# V3_1.net
KiCad netlist of a schematic drawn in EasyEDA Pro
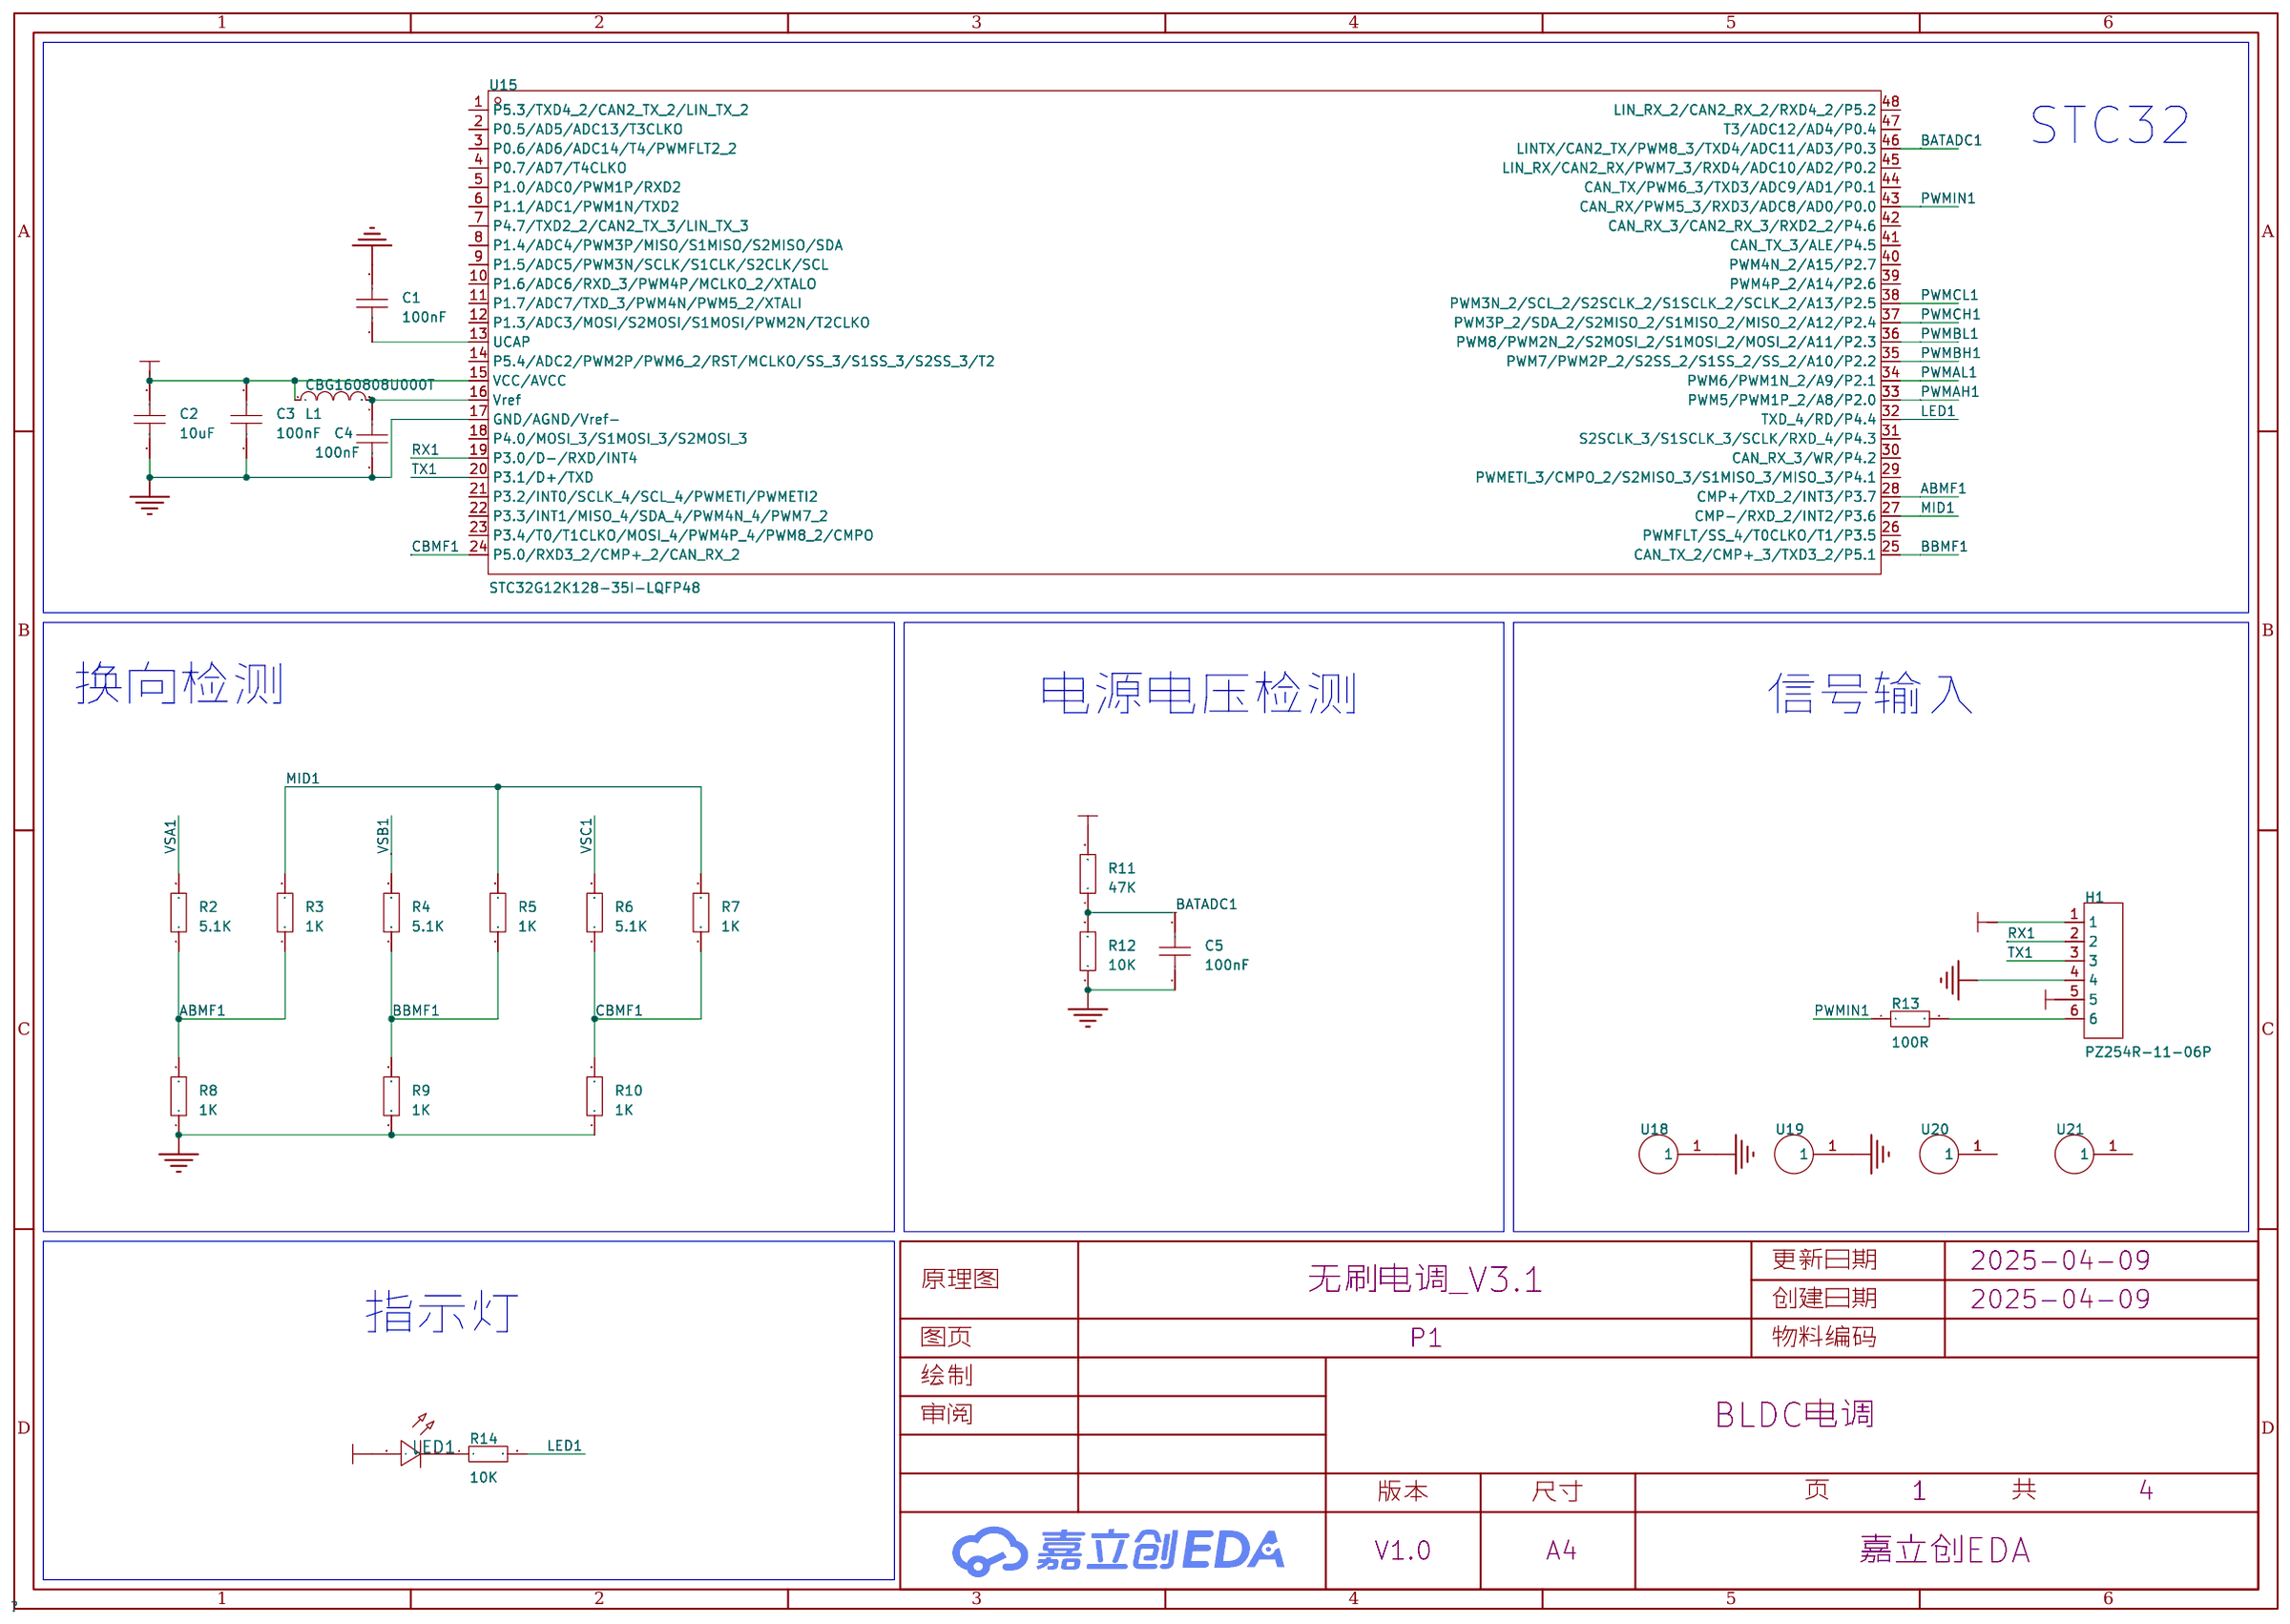
[diagram p0: P1]
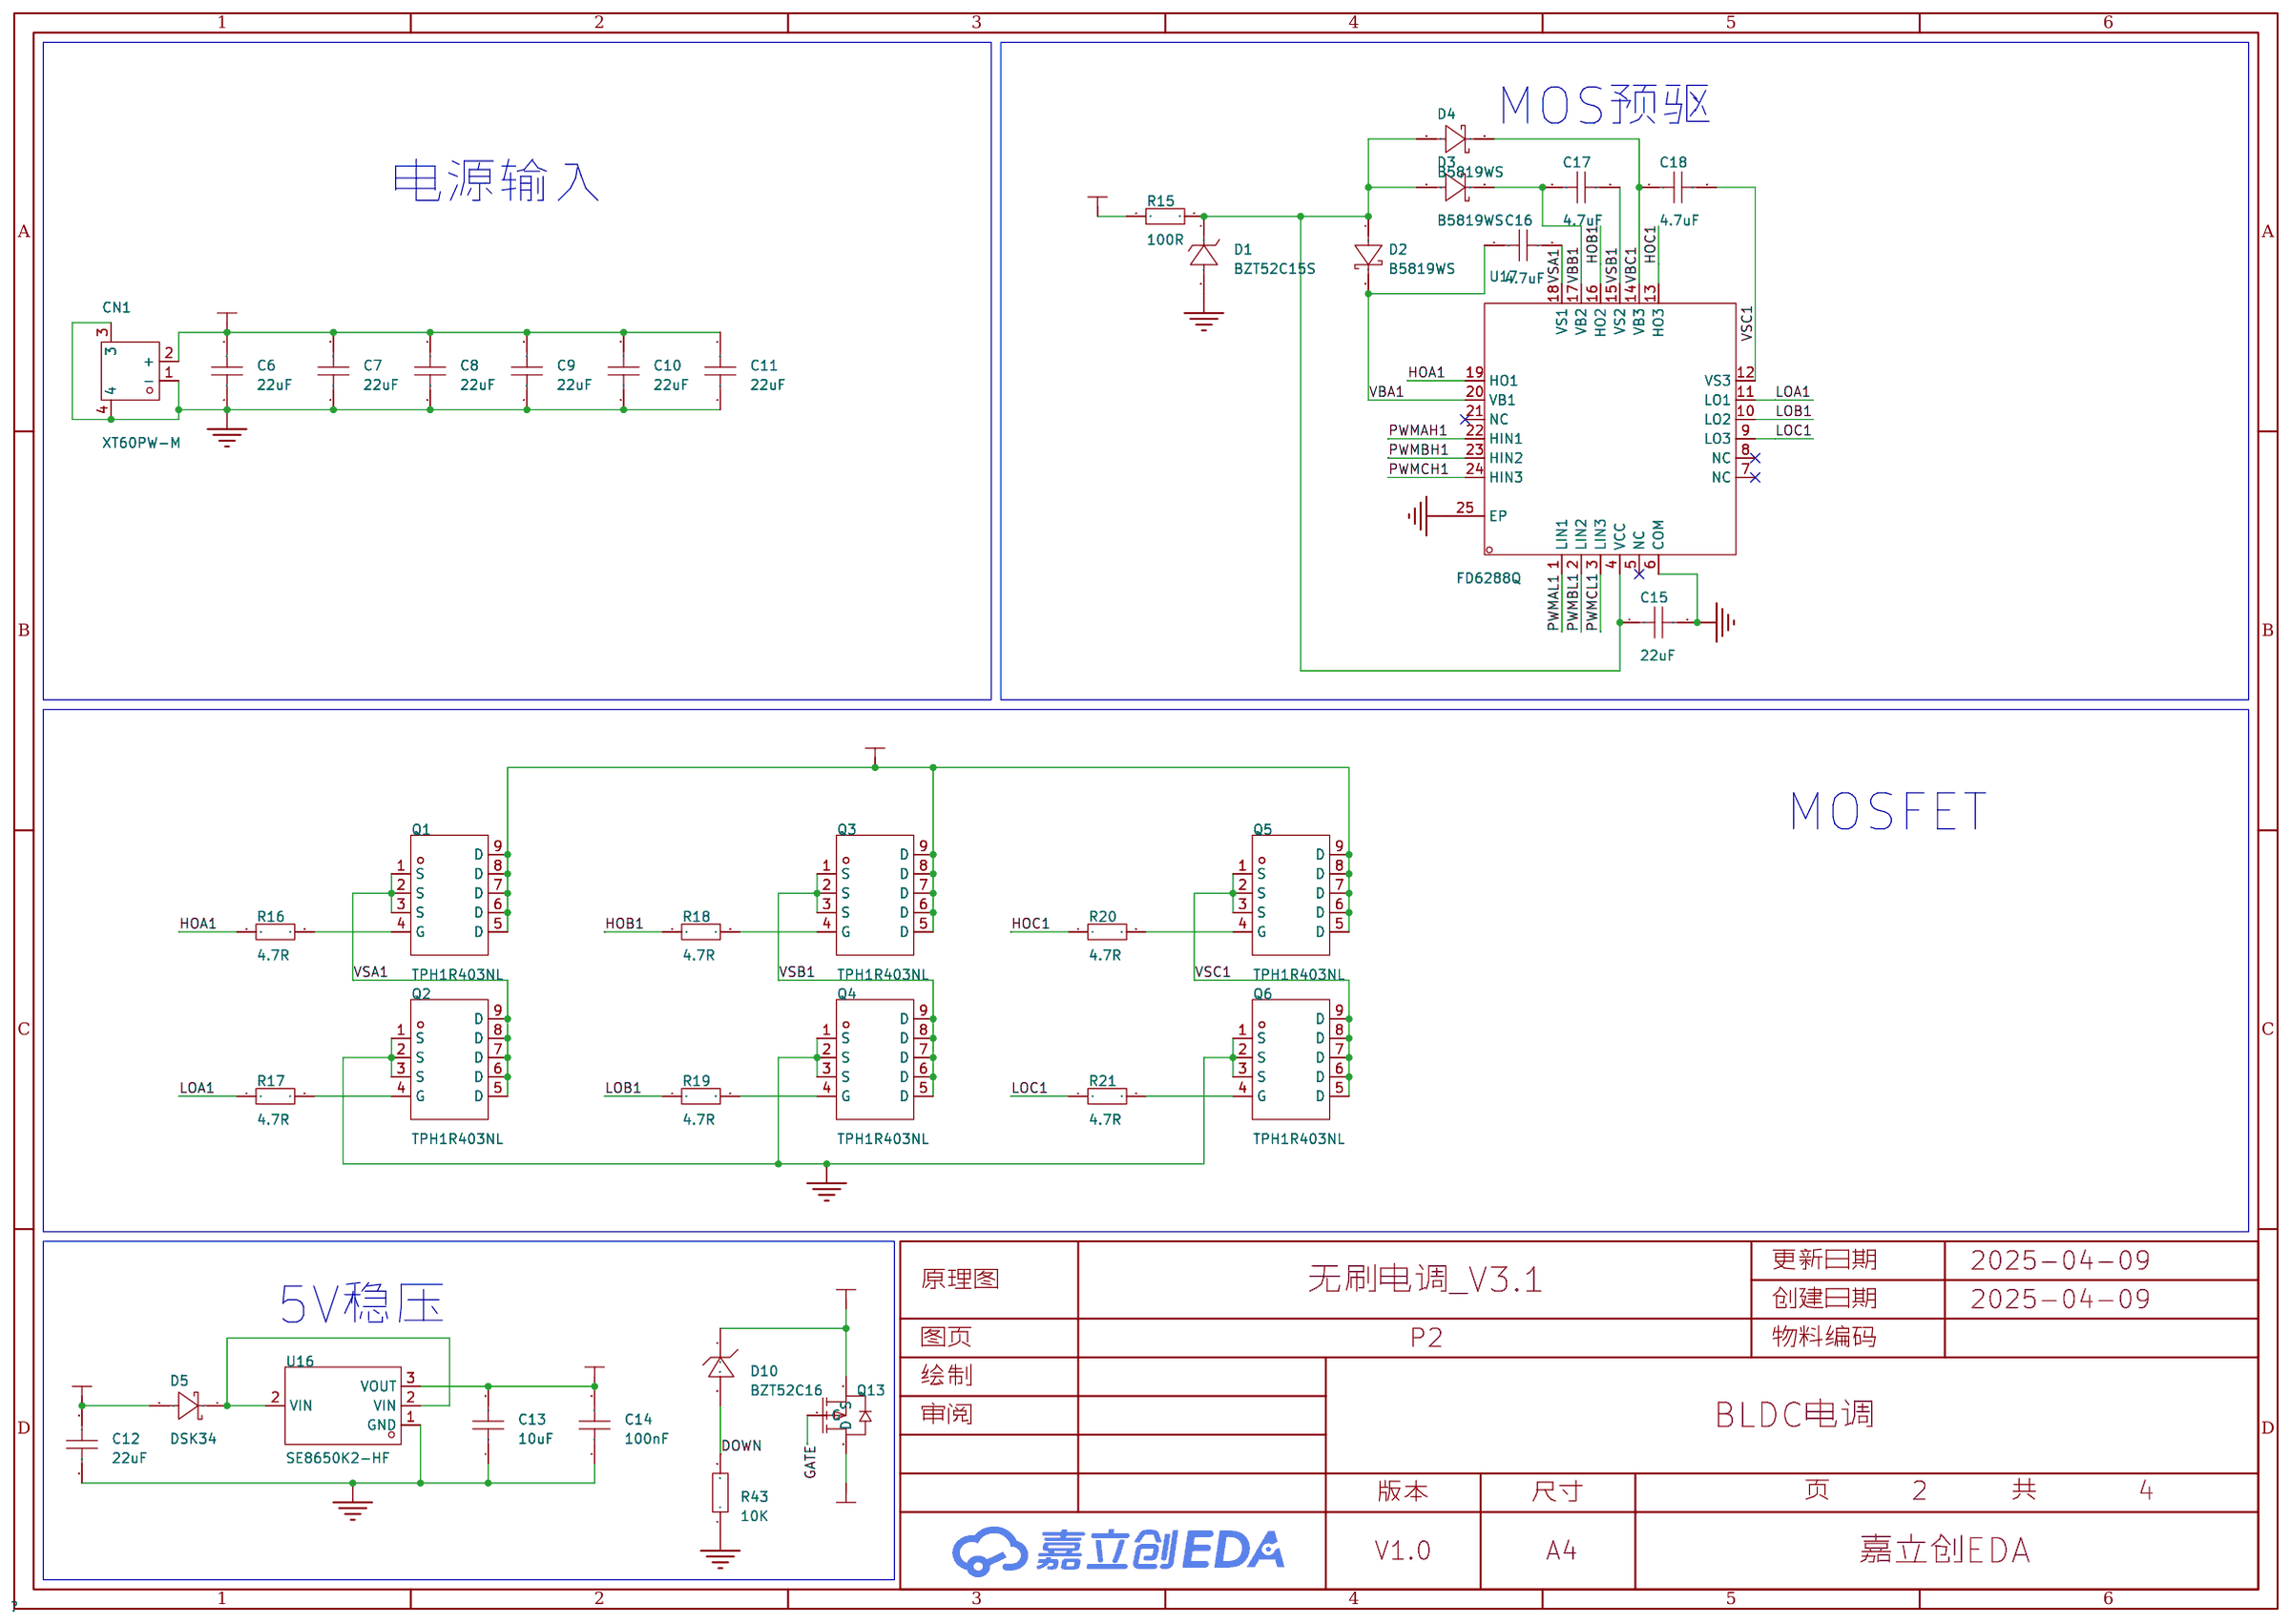
[diagram p1: P2]
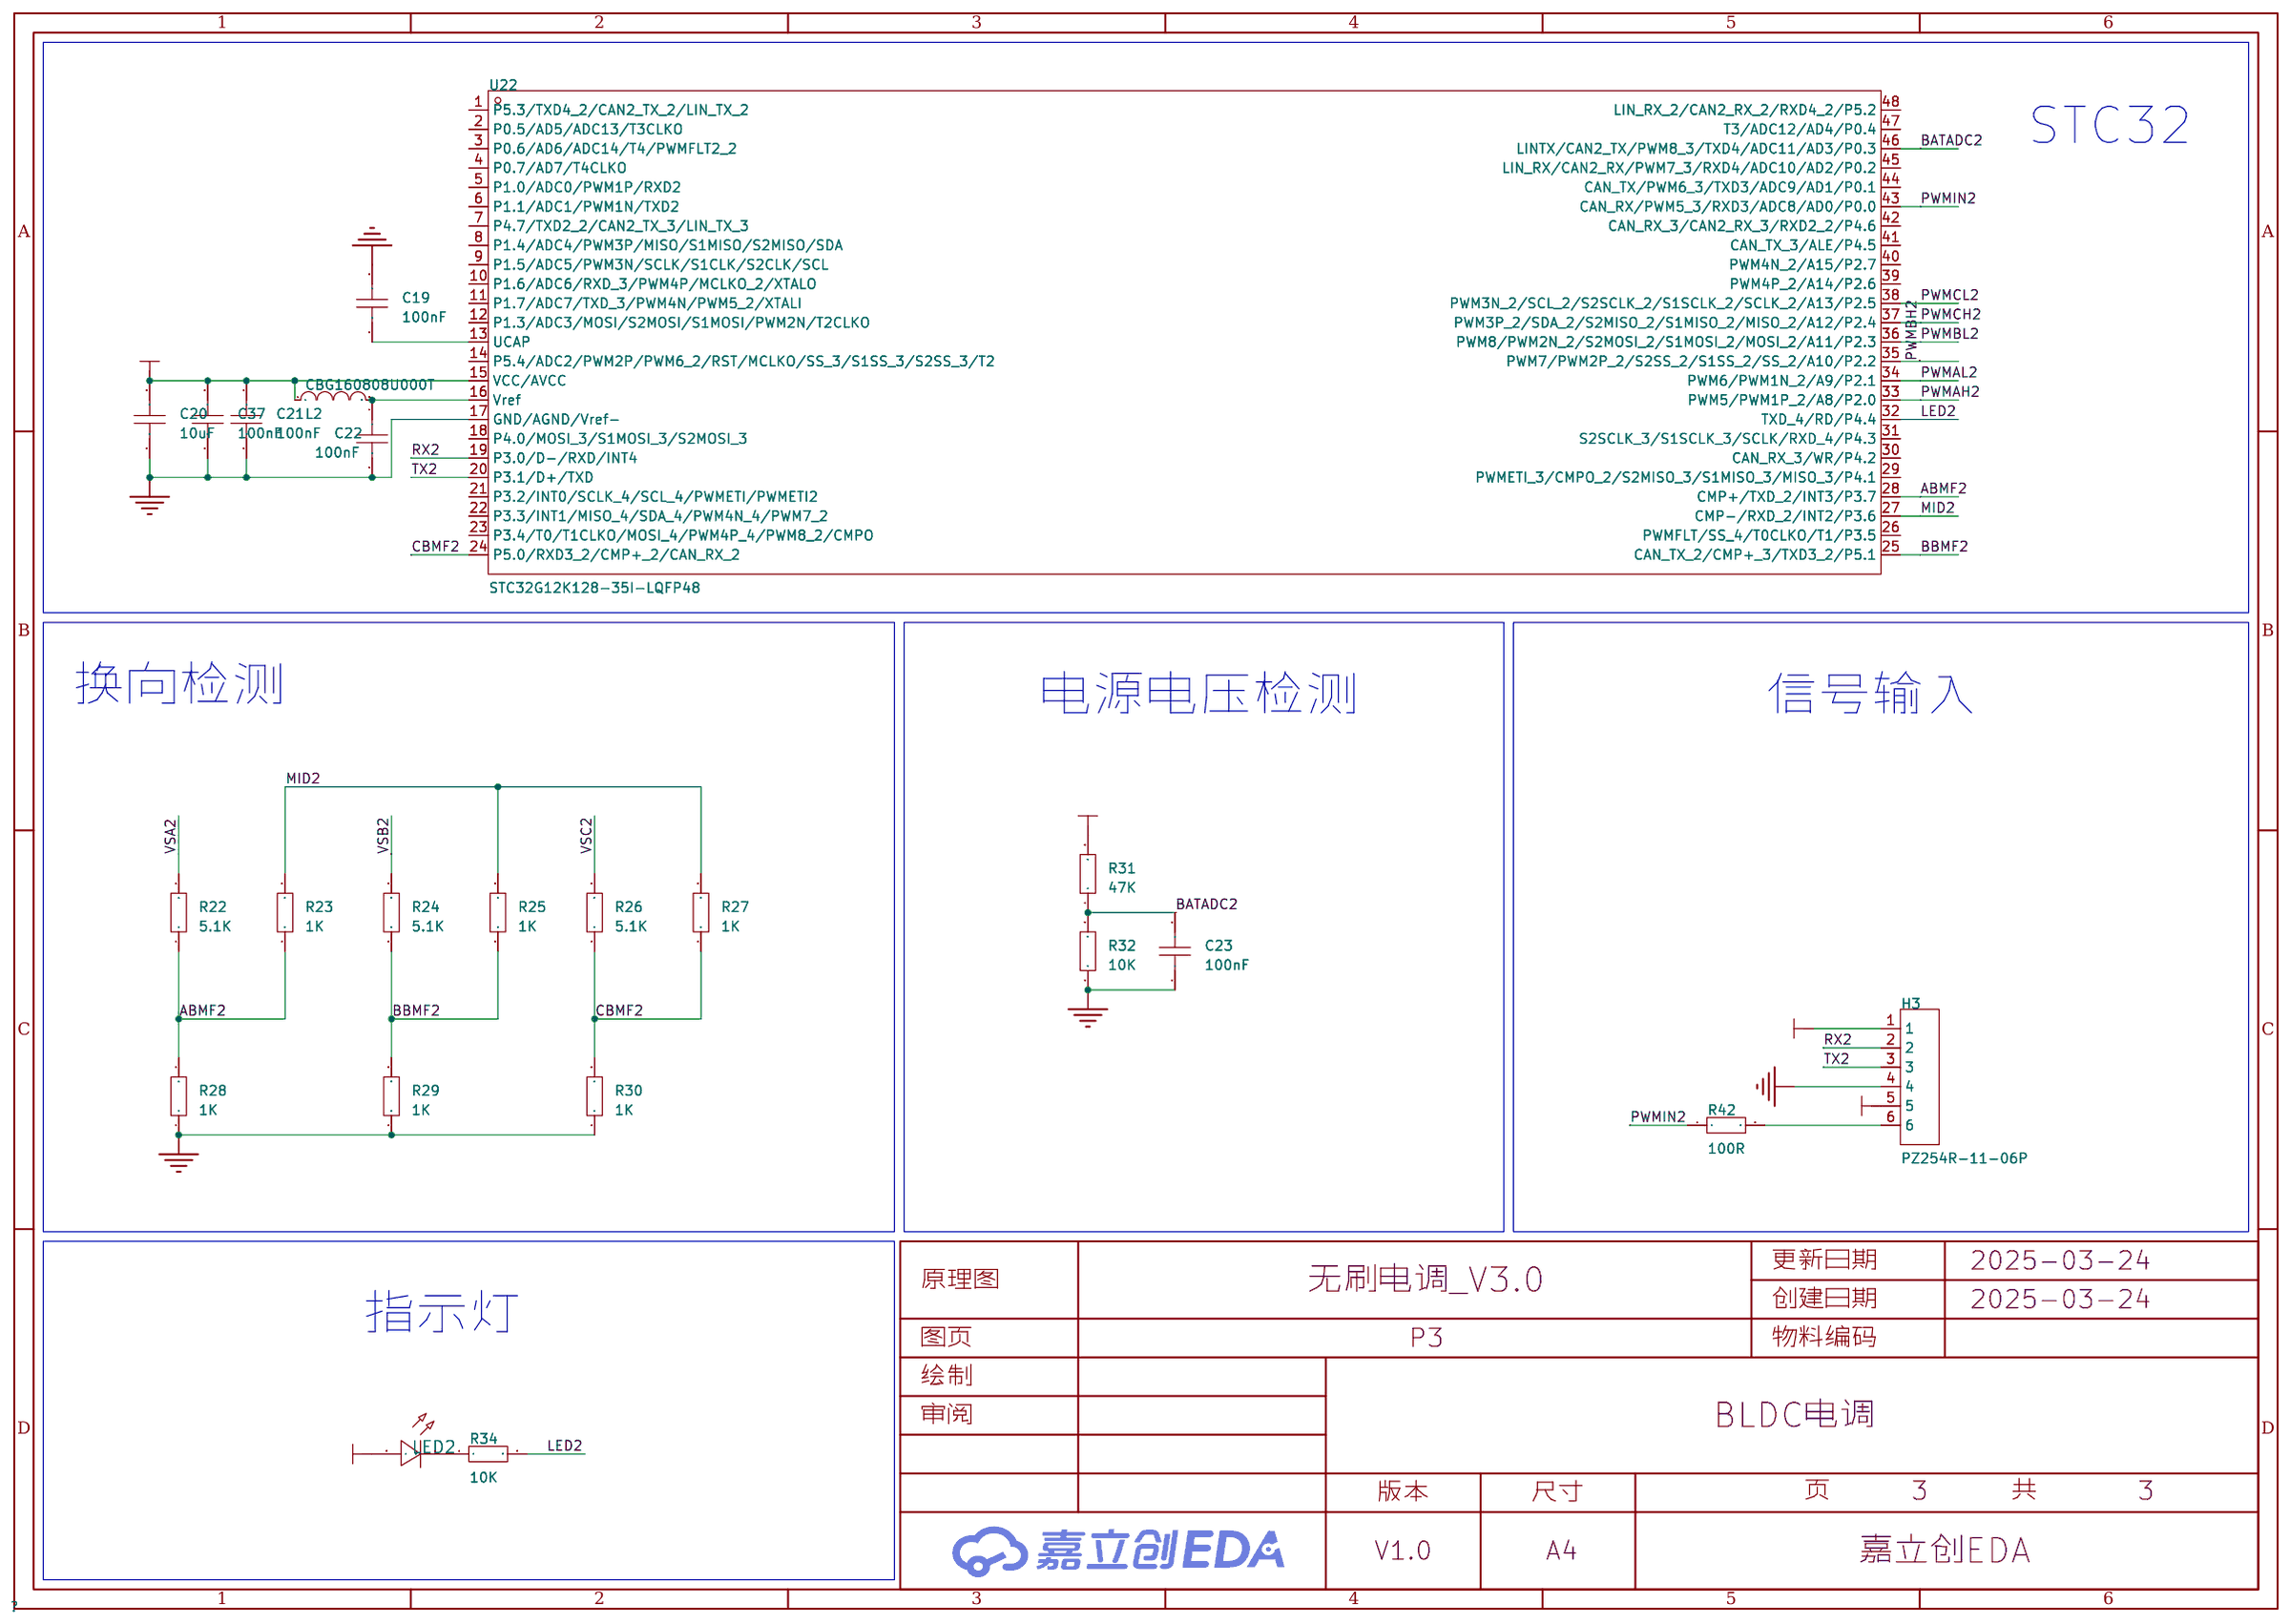
[diagram p2: P3]
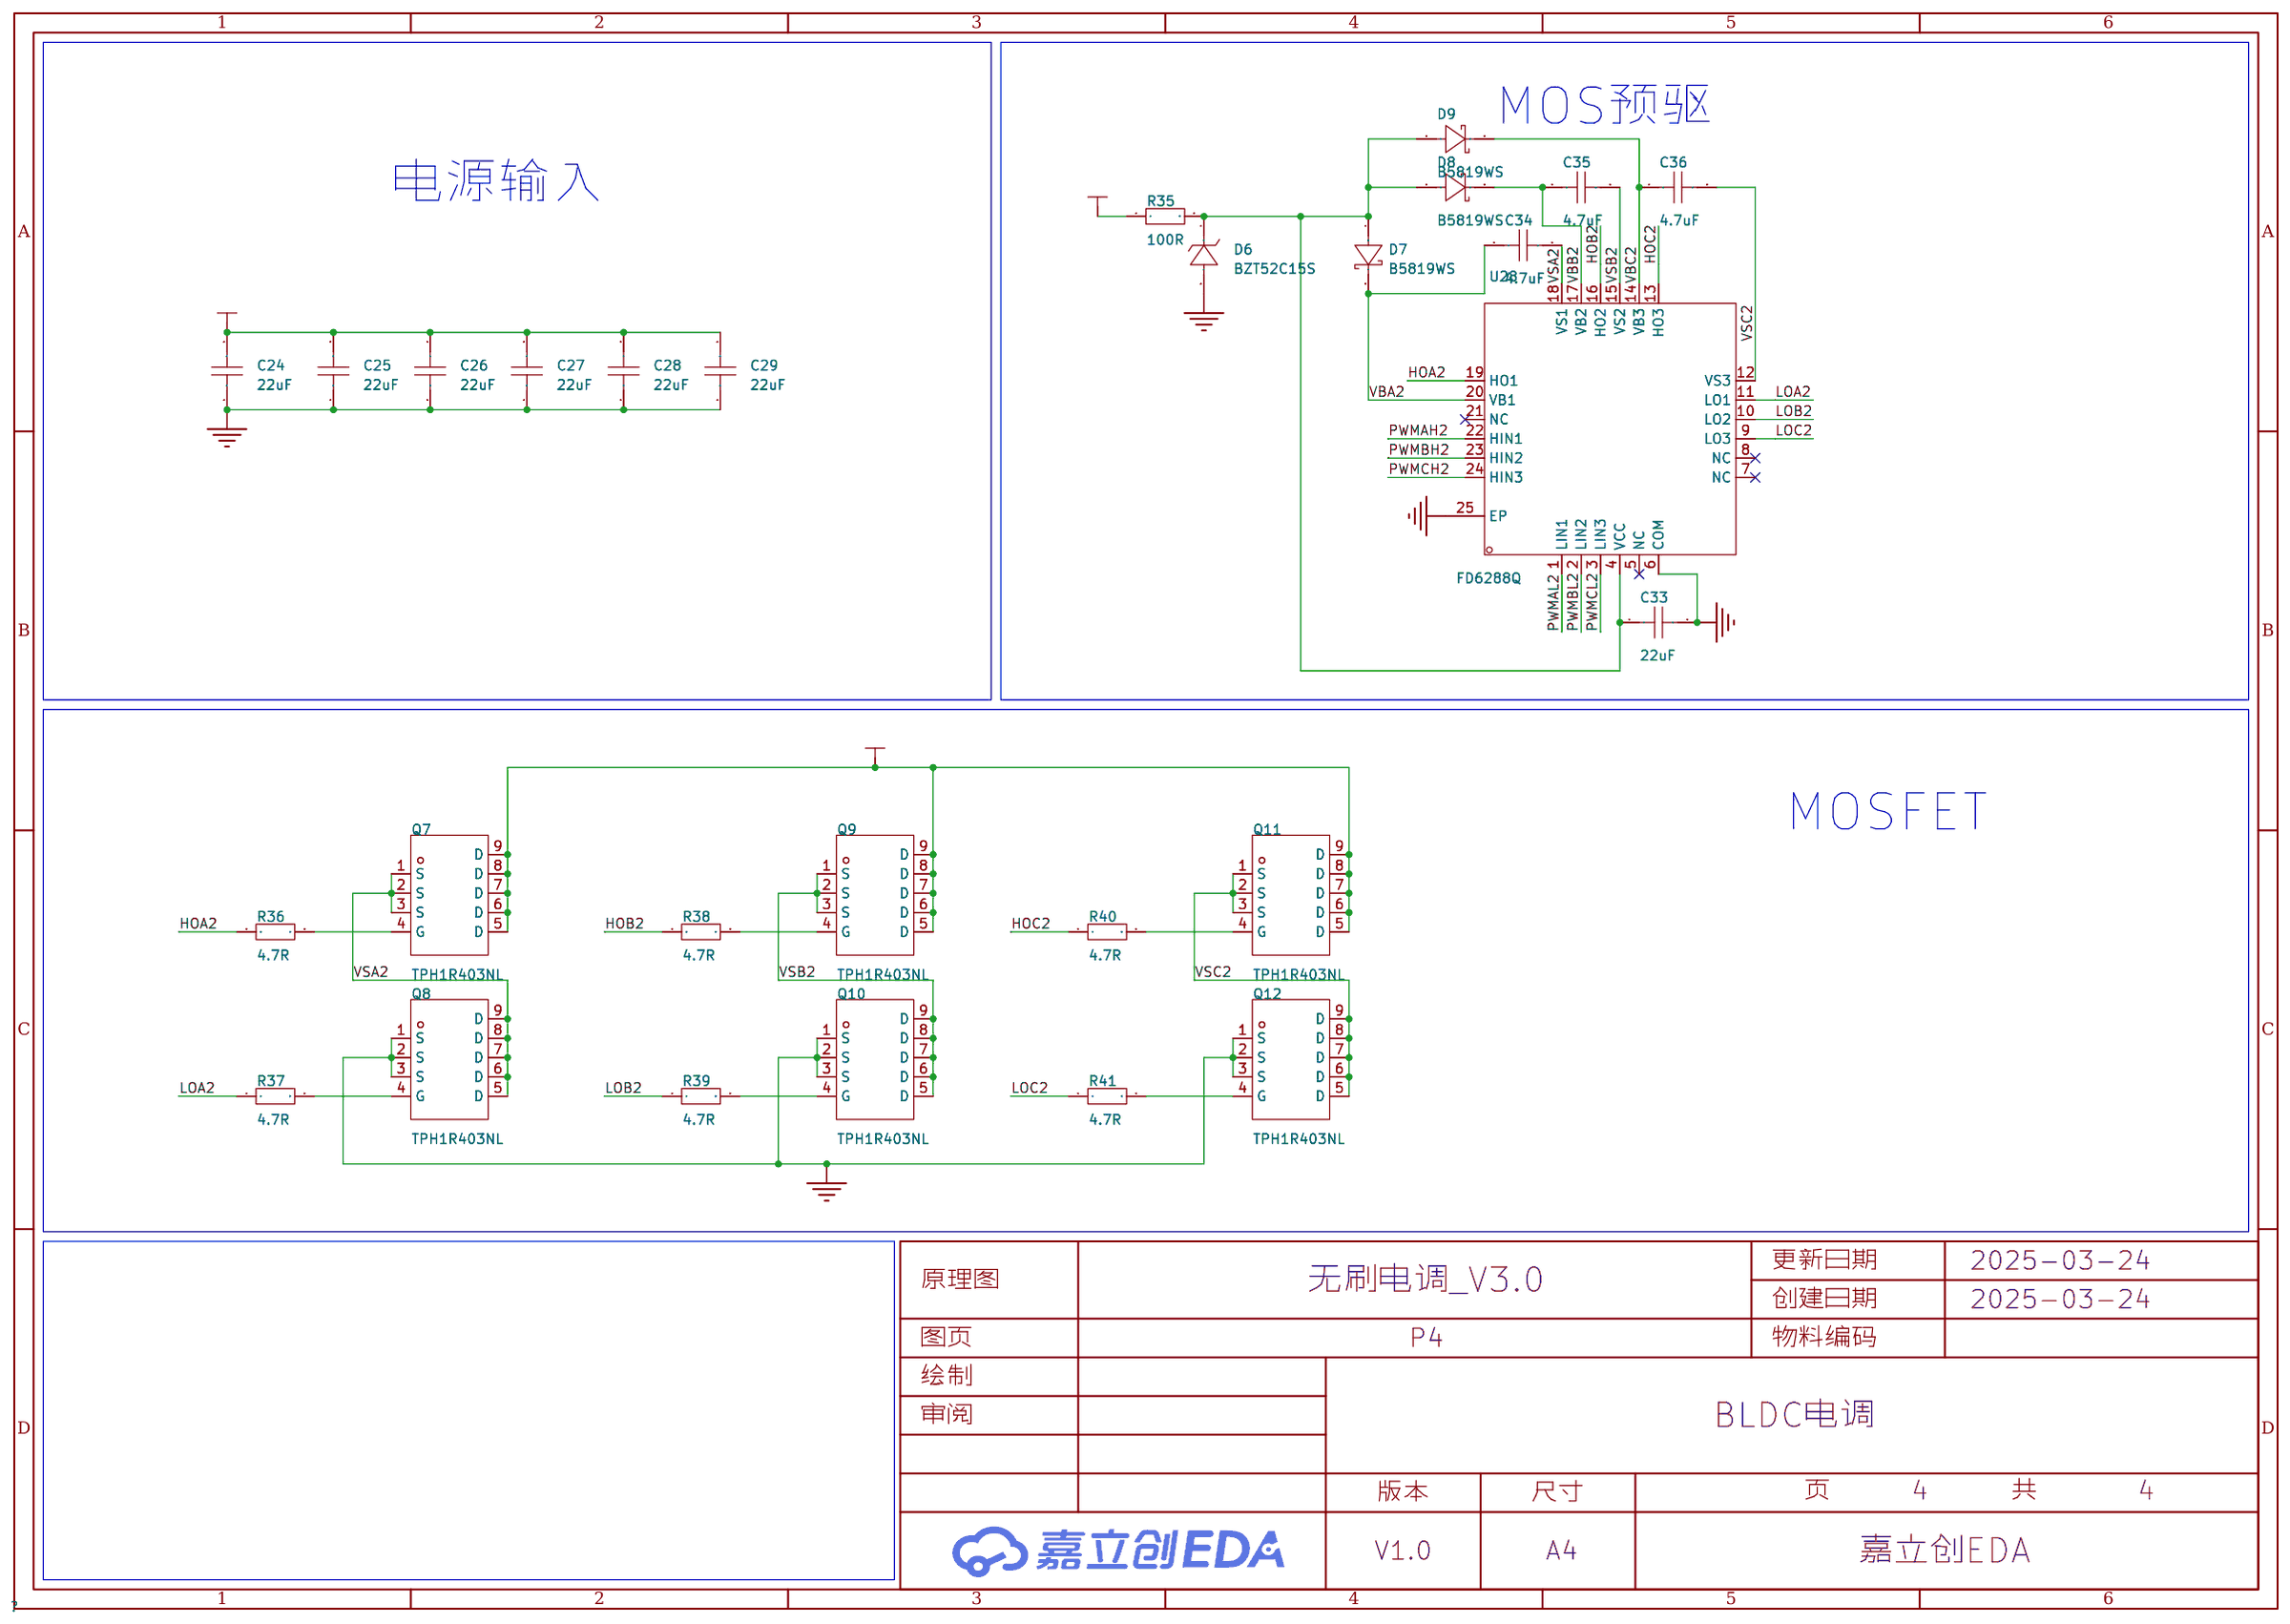
[diagram p3: P4]

(export (version "E")
  (design (tool "Eeschema 10.0.6"))
  (components
    (comp (ref "C1")
      (value "100nF")
      (footprint "easyedapro:C0603")
      (libsource (lib "easyedapro") (part "CapAcitance"))
    )
    (comp (ref "C2")
      (value "10uF")
      (footprint "easyedapro:C0603")
      (libsource (lib "easyedapro") (part "CapAcitance"))
    )
    (comp (ref "C3")
      (value "100nF")
      (footprint "easyedapro:C0603")
      (libsource (lib "easyedapro") (part "CapAcitance"))
    )
    (comp (ref "C4")
      (value "100nF")
      (footprint "easyedapro:C0603")
      (libsource (lib "easyedapro") (part "CapAcitance"))
    )
    (comp (ref "C5")
      (value "100nF")
      (footprint "easyedapro:C0603")
      (libsource (lib "easyedapro") (part "CapAcitance"))
    )
    (comp (ref "H1")
      (value "PZ254R-11-06P")
      (footprint "easyedapro:HDR-TH_6P-P2.54-H-M-W10.4")
      (fields (field (name "Manufacturer") "XFCN(兴飞)"))
      (libsource (lib "easyedapro") (part "PZ254R-11-06P"))
    )
    (comp (ref "L1")
      (value "CBG160808U000T")
      (footprint "easyedapro:L0603")
      (description "标称阻抗@测试频率:0Ω@100MHz;直流电阻(RDC):100mΩ;")
      (fields (field (name "Manufacturer") "FH(风华)"))
      (libsource (lib "easyedapro") (part "CBG160808U000T"))
    )
    (comp (ref "LED1")
      (value "~")
      (footprint "easyedapro:LED_0603")
      (libsource (lib "easyedapro") (part "LED_R"))
    )
    (comp (ref "R2") (value "5.1K") (footprint "easyedapro:R0603") (libsource (lib "easyedapro") (part "电阻")))
    (comp (ref "R3") (value "1K") (footprint "easyedapro:R0603") (libsource (lib "easyedapro") (part "电阻")))
    (comp (ref "R4") (value "5.1K") (footprint "easyedapro:R0603") (libsource (lib "easyedapro") (part "电阻")))
    (comp (ref "R5") (value "1K") (footprint "easyedapro:R0603") (libsource (lib "easyedapro") (part "电阻")))
    (comp (ref "R6") (value "5.1K") (footprint "easyedapro:R0603") (libsource (lib "easyedapro") (part "电阻")))
    (comp (ref "R7") (value "1K") (footprint "easyedapro:R0603") (libsource (lib "easyedapro") (part "电阻")))
    (comp (ref "R8") (value "1K") (footprint "easyedapro:R0603") (libsource (lib "easyedapro") (part "电阻")))
    (comp (ref "R9") (value "1K") (footprint "easyedapro:R0603") (libsource (lib "easyedapro") (part "电阻")))
    (comp (ref "R10") (value "1K") (footprint "easyedapro:R0603") (libsource (lib "easyedapro") (part "电阻")))
    (comp (ref "R11") (value "47K") (footprint "easyedapro:R0603") (libsource (lib "easyedapro") (part "电阻")))
    (comp (ref "R12") (value "10K") (footprint "easyedapro:R0603") (libsource (lib "easyedapro") (part "电阻")))
    (comp (ref "R13")
      (value "100R")
      (footprint "easyedapro:R0603")
      (libsource (lib "easyedapro") (part "电阻"))
    )
    (comp (ref "R14") (value "10K") (footprint "easyedapro:R0603") (libsource (lib "easyedapro") (part "电阻")))
    (comp (ref "U15")
      (value "STC32G12K128-35I-LQFP48")
      (footprint "easyedapro:LQFP-48_L7.0-W7.0-P0.50-LS9.0-BL")
      (fields (field (name "Manufacturer") "STC(宏晶)"))
      (libsource (lib "easyedapro") (part "STC32G12K128-35I-LQFP48"))
    )
    (comp (ref "U18")
      (value "~")
      (footprint "easyedapro:M3螺丝孔")
      (libsource (lib "easyedapro") (part "M3螺丝孔"))
    )
    (comp (ref "U19")
      (value "~")
      (footprint "easyedapro:M3螺丝孔")
      (libsource (lib "easyedapro") (part "M3螺丝孔"))
    )
    (comp (ref "U20")
      (value "~")
      (footprint "easyedapro:M3螺丝孔")
      (libsource (lib "easyedapro") (part "M3螺丝孔"))
    )
    (comp (ref "U21")
      (value "~")
      (footprint "easyedapro:M3螺丝孔")
      (libsource (lib "easyedapro") (part "M3螺丝孔"))
    )
    (comp (ref "C6")
      (value "22uF")
      (footprint "easyedapro:C0603")
      (libsource (lib "easyedapro") (part "CapAcitance"))
    )
    (comp (ref "C7")
      (value "22uF")
      (footprint "easyedapro:C0603")
      (libsource (lib "easyedapro") (part "CapAcitance"))
    )
    (comp (ref "C8")
      (value "22uF")
      (footprint "easyedapro:C0603")
      (libsource (lib "easyedapro") (part "CapAcitance"))
    )
    (comp (ref "C9")
      (value "22uF")
      (footprint "easyedapro:C0603")
      (libsource (lib "easyedapro") (part "CapAcitance"))
    )
    (comp (ref "C10")
      (value "22uF")
      (footprint "easyedapro:C0603")
      (libsource (lib "easyedapro") (part "CapAcitance"))
    )
    (comp (ref "C11")
      (value "22uF")
      (footprint "easyedapro:C0603")
      (libsource (lib "easyedapro") (part "CapAcitance"))
    )
    (comp (ref "C12")
      (value "22uF")
      (footprint "easyedapro:C0603")
      (libsource (lib "easyedapro") (part "CapAcitance"))
    )
    (comp (ref "C13")
      (value "10uF")
      (footprint "easyedapro:C0603")
      (libsource (lib "easyedapro") (part "CapAcitance"))
    )
    (comp (ref "C14")
      (value "100nF")
      (footprint "easyedapro:C0603")
      (libsource (lib "easyedapro") (part "CapAcitance"))
    )
    (comp (ref "C15")
      (value "22uF")
      (footprint "easyedapro:C0603")
      (libsource (lib "easyedapro") (part "CapAcitance"))
    )
    (comp (ref "C16")
      (value "4.7uF")
      (footprint "easyedapro:C0603")
      (libsource (lib "easyedapro") (part "CapAcitance"))
    )
    (comp (ref "C17")
      (value "4.7uF")
      (footprint "easyedapro:C0603")
      (libsource (lib "easyedapro") (part "CapAcitance"))
    )
    (comp (ref "C18")
      (value "4.7uF")
      (footprint "easyedapro:C0603")
      (libsource (lib "easyedapro") (part "CapAcitance"))
    )
    (comp (ref "CN1")
      (value "XT60PW-M")
      (footprint "easyedapro:CONN-TH_XT60PW-M")
      (description "类别:-;类型1:-;")
      (fields (field (name "Manufacturer") "AMASS(艾迈斯)"))
      (libsource (lib "easyedapro") (part "XT60PW-M"))
    )
    (comp (ref "D1")
      (value "BZT52C15S")
      (footprint "easyedapro:SOD-323_L1.7-W1.3-LS2.6-RD")
      (description "二极管配置:独立式;稳压值(标称值):15V;稳压值(范围):13.8V~15.6V;功率(Pd):200mW;")
      (fields (field (name "Manufacturer") "宏迦橙"))
      (libsource (lib "easyedapro") (part "BZT52C15S_C19077448"))
    )
    (comp (ref "D2")
      (value "B5819WS")
      (footprint "easyedapro:SOD-323_L1.7-W1.3-LS2.5-FD")
      (description "二极管配置:独立式;直流反向耐压(Vr):40V;平均整流电流(Io):1A;正向压降(Vf):600mV@1.0A;")
      (fields (field (name "Manufacturer") "宏迦橙"))
      (libsource (lib "easyedapro") (part "B5819WS_C7420331"))
    )
    (comp (ref "D3")
      (value "B5819WS")
      (footprint "easyedapro:SOD-323_L1.7-W1.3-LS2.5-FD")
      (description "二极管配置:独立式;直流反向耐压(Vr):40V;平均整流电流(Io):1A;正向压降(Vf):600mV@1.0A;")
      (fields (field (name "Manufacturer") "宏迦橙"))
      (libsource (lib "easyedapro") (part "B5819WS_C7420331"))
    )
    (comp (ref "D4")
      (value "B5819WS")
      (footprint "easyedapro:SOD-323_L1.7-W1.3-LS2.5-FD")
      (description "二极管配置:独立式;直流反向耐压(Vr):40V;平均整流电流(Io):1A;正向压降(Vf):600mV@1.0A;")
      (fields (field (name "Manufacturer") "宏迦橙"))
      (libsource (lib "easyedapro") (part "B5819WS_C7420331"))
    )
    (comp (ref "D5")
      (value "DSK34")
      (footprint "easyedapro:SOD-123_L2.8-W1.8-LS3.7-RD")
      (description "二极管配置:-;正向压降(Vf):550mV@3A;直流反向耐压(Vr):40V;整流电流:3A;")
      (fields (field (name "Manufacturer") "FUXINSEMI(富芯森美)"))
      (libsource (lib "easyedapro") (part "DSK34_C908230"))
    )
    (comp (ref "D10")
      (value "BZT52C16")
      (footprint "easyedapro:SOD-123_L2.7-W1.6-LS3.7-RD")
      (description "二极管配置:独立式;稳压值(标称值):16V;稳压值(范围):15.3V~17.1V;功率:500mW;精度:-;")
      (fields (field (name "Manufacturer") "BORN(伯恩半导体)"))
      (libsource (lib "easyedapro") (part "BZT52C16_C266570"))
    )
    (comp (ref "Q1")
      (value "TPH1R403NL")
      (footprint "easyedapro:DSOP-8_L5.0-W5.0-P1.27-LS6.0-BL-EP")
      (fields (field (name "Manufacturer") "TOSHIBA(东芝)"))
      (libsource (lib "easyedapro") (part "TPH1R403NL"))
    )
    (comp (ref "Q2")
      (value "TPH1R403NL")
      (footprint "easyedapro:DSOP-8_L5.0-W5.0-P1.27-LS6.0-BL-EP")
      (fields (field (name "Manufacturer") "TOSHIBA(东芝)"))
      (libsource (lib "easyedapro") (part "TPH1R403NL"))
    )
    (comp (ref "Q3")
      (value "TPH1R403NL")
      (footprint "easyedapro:DSOP-8_L5.0-W5.0-P1.27-LS6.0-BL-EP")
      (fields (field (name "Manufacturer") "TOSHIBA(东芝)"))
      (libsource (lib "easyedapro") (part "TPH1R403NL"))
    )
    (comp (ref "Q4")
      (value "TPH1R403NL")
      (footprint "easyedapro:DSOP-8_L5.0-W5.0-P1.27-LS6.0-BL-EP")
      (fields (field (name "Manufacturer") "TOSHIBA(东芝)"))
      (libsource (lib "easyedapro") (part "TPH1R403NL"))
    )
    (comp (ref "Q5")
      (value "TPH1R403NL")
      (footprint "easyedapro:DSOP-8_L5.0-W5.0-P1.27-LS6.0-BL-EP")
      (fields (field (name "Manufacturer") "TOSHIBA(东芝)"))
      (libsource (lib "easyedapro") (part "TPH1R403NL"))
    )
    (comp (ref "Q6")
      (value "TPH1R403NL")
      (footprint "easyedapro:DSOP-8_L5.0-W5.0-P1.27-LS6.0-BL-EP")
      (fields (field (name "Manufacturer") "TOSHIBA(东芝)"))
      (libsource (lib "easyedapro") (part "TPH1R403NL"))
    )
    (comp (ref "Q13")
      (value "~")
      (footprint "easyedapro:AO3401A_SOT-23-3")
      (libsource (lib "easyedapro") (part "P_MOS"))
    )
    (comp (ref "R15")
      (value "100R")
      (footprint "easyedapro:R0603")
      (libsource (lib "easyedapro") (part "电阻"))
    )
    (comp (ref "R16")
      (value "4.7R")
      (footprint "easyedapro:R0603")
      (libsource (lib "easyedapro") (part "电阻"))
    )
    (comp (ref "R17")
      (value "4.7R")
      (footprint "easyedapro:R0603")
      (libsource (lib "easyedapro") (part "电阻"))
    )
    (comp (ref "R18")
      (value "4.7R")
      (footprint "easyedapro:R0603")
      (libsource (lib "easyedapro") (part "电阻"))
    )
    (comp (ref "R19")
      (value "4.7R")
      (footprint "easyedapro:R0603")
      (libsource (lib "easyedapro") (part "电阻"))
    )
    (comp (ref "R20")
      (value "4.7R")
      (footprint "easyedapro:R0603")
      (libsource (lib "easyedapro") (part "电阻"))
    )
    (comp (ref "R21")
      (value "4.7R")
      (footprint "easyedapro:R0603")
      (libsource (lib "easyedapro") (part "电阻"))
    )
    (comp (ref "R43") (value "10K") (footprint "easyedapro:R0603") (libsource (lib "easyedapro") (part "电阻")))
    (comp (ref "U16")
      (value "SE8650K2-HF")
      (footprint "easyedapro:SOT-89-3_L4.5-W2.5-P1.50-LS4.2-BR")
      (description "输出类型:固定;最大输入电压:80V;输出电压:5V;最大输出电流:-;电源纹波抑制比(PSRR):85dB;输出极性:正极;")
      (fields (field (name "Manufacturer") "SEAWARD(思旺)"))
      (libsource (lib "easyedapro") (part "SE8650K2-HF"))
    )
    (comp (ref "U17")
      (value "FD6288Q")
      (footprint "easyedapro:QFN-24_L4.0-W4.0-P0.50-BL-EP2.6")
      (fields (field (name "Manufacturer") "Fortior Tech(峰岹)"))
      (libsource (lib "easyedapro") (part "FD6288Q_C328453"))
    )
    (comp (ref "C19")
      (value "100nF")
      (footprint "easyedapro:C0603")
      (libsource (lib "easyedapro") (part "CapAcitance"))
    )
    (comp (ref "C20")
      (value "10uF")
      (footprint "easyedapro:C0603")
      (libsource (lib "easyedapro") (part "CapAcitance"))
    )
    (comp (ref "C21")
      (value "100nF")
      (footprint "easyedapro:C0603")
      (libsource (lib "easyedapro") (part "CapAcitance"))
    )
    (comp (ref "C22")
      (value "100nF")
      (footprint "easyedapro:C0603")
      (libsource (lib "easyedapro") (part "CapAcitance"))
    )
    (comp (ref "C23")
      (value "100nF")
      (footprint "easyedapro:C0603")
      (libsource (lib "easyedapro") (part "CapAcitance"))
    )
    (comp (ref "C37")
      (value "100nF")
      (footprint "easyedapro:C0603")
      (libsource (lib "easyedapro") (part "CapAcitance"))
    )
    (comp (ref "H3")
      (value "PZ254R-11-06P")
      (footprint "easyedapro:HDR-TH_6P-P2.54-H-M-W10.4")
      (fields (field (name "Manufacturer") "XFCN(兴飞)"))
      (libsource (lib "easyedapro") (part "PZ254R-11-06P"))
    )
    (comp (ref "L2")
      (value "CBG160808U000T")
      (footprint "easyedapro:L0603")
      (description "标称阻抗@测试频率:0Ω@100MHz;直流电阻(RDC):100mΩ;")
      (fields (field (name "Manufacturer") "FH(风华)"))
      (libsource (lib "easyedapro") (part "CBG160808U000T"))
    )
    (comp (ref "LED2")
      (value "~")
      (footprint "easyedapro:LED_0603")
      (libsource (lib "easyedapro") (part "LED_R"))
    )
    (comp (ref "R22")
      (value "5.1K")
      (footprint "easyedapro:R0603")
      (libsource (lib "easyedapro") (part "电阻"))
    )
    (comp (ref "R23") (value "1K") (footprint "easyedapro:R0603") (libsource (lib "easyedapro") (part "电阻")))
    (comp (ref "R24")
      (value "5.1K")
      (footprint "easyedapro:R0603")
      (libsource (lib "easyedapro") (part "电阻"))
    )
    (comp (ref "R25") (value "1K") (footprint "easyedapro:R0603") (libsource (lib "easyedapro") (part "电阻")))
    (comp (ref "R26")
      (value "5.1K")
      (footprint "easyedapro:R0603")
      (libsource (lib "easyedapro") (part "电阻"))
    )
    (comp (ref "R27") (value "1K") (footprint "easyedapro:R0603") (libsource (lib "easyedapro") (part "电阻")))
    (comp (ref "R28") (value "1K") (footprint "easyedapro:R0603") (libsource (lib "easyedapro") (part "电阻")))
    (comp (ref "R29") (value "1K") (footprint "easyedapro:R0603") (libsource (lib "easyedapro") (part "电阻")))
    (comp (ref "R30") (value "1K") (footprint "easyedapro:R0603") (libsource (lib "easyedapro") (part "电阻")))
    (comp (ref "R31") (value "47K") (footprint "easyedapro:R0603") (libsource (lib "easyedapro") (part "电阻")))
    (comp (ref "R32") (value "10K") (footprint "easyedapro:R0603") (libsource (lib "easyedapro") (part "电阻")))
    (comp (ref "R34") (value "10K") (footprint "easyedapro:R0603") (libsource (lib "easyedapro") (part "电阻")))
    (comp (ref "R42")
      (value "100R")
      (footprint "easyedapro:R0603")
      (libsource (lib "easyedapro") (part "电阻"))
    )
    (comp (ref "U22")
      (value "STC32G12K128-35I-LQFP48")
      (footprint "easyedapro:LQFP-48_L7.0-W7.0-P0.50-LS9.0-BL")
      (fields (field (name "Manufacturer") "STC(宏晶)"))
      (libsource (lib "easyedapro") (part "STC32G12K128-35I-LQFP48"))
    )
    (comp (ref "C24")
      (value "22uF")
      (footprint "easyedapro:C0603")
      (libsource (lib "easyedapro") (part "CapAcitance"))
    )
    (comp (ref "C25")
      (value "22uF")
      (footprint "easyedapro:C0603")
      (libsource (lib "easyedapro") (part "CapAcitance"))
    )
    (comp (ref "C26")
      (value "22uF")
      (footprint "easyedapro:C0603")
      (libsource (lib "easyedapro") (part "CapAcitance"))
    )
    (comp (ref "C27")
      (value "22uF")
      (footprint "easyedapro:C0603")
      (libsource (lib "easyedapro") (part "CapAcitance"))
    )
    (comp (ref "C28")
      (value "22uF")
      (footprint "easyedapro:C0603")
      (libsource (lib "easyedapro") (part "CapAcitance"))
    )
    (comp (ref "C29")
      (value "22uF")
      (footprint "easyedapro:C0603")
      (libsource (lib "easyedapro") (part "CapAcitance"))
    )
    (comp (ref "C33")
      (value "22uF")
      (footprint "easyedapro:C0603")
      (libsource (lib "easyedapro") (part "CapAcitance"))
    )
    (comp (ref "C34")
      (value "4.7uF")
      (footprint "easyedapro:C0603")
      (libsource (lib "easyedapro") (part "CapAcitance"))
    )
    (comp (ref "C35")
      (value "4.7uF")
      (footprint "easyedapro:C0603")
      (libsource (lib "easyedapro") (part "CapAcitance"))
    )
    (comp (ref "C36")
      (value "4.7uF")
      (footprint "easyedapro:C0603")
      (libsource (lib "easyedapro") (part "CapAcitance"))
    )
    (comp (ref "D6")
      (value "BZT52C15S")
      (footprint "easyedapro:SOD-323_L1.7-W1.3-LS2.6-RD")
      (description "二极管配置:独立式;稳压值(标称值):15V;稳压值(范围):13.8V~15.6V;功率(Pd):200mW;")
      (fields (field (name "Manufacturer") "宏迦橙"))
      (libsource (lib "easyedapro") (part "BZT52C15S_C19077448"))
    )
    (comp (ref "D7")
      (value "B5819WS")
      (footprint "easyedapro:SOD-323_L1.7-W1.3-LS2.5-FD")
      (description "二极管配置:独立式;直流反向耐压(Vr):40V;平均整流电流(Io):1A;正向压降(Vf):600mV@1.0A;")
      (fields (field (name "Manufacturer") "宏迦橙"))
      (libsource (lib "easyedapro") (part "B5819WS_C7420331"))
    )
    (comp (ref "D8")
      (value "B5819WS")
      (footprint "easyedapro:SOD-323_L1.7-W1.3-LS2.5-FD")
      (description "二极管配置:独立式;直流反向耐压(Vr):40V;平均整流电流(Io):1A;正向压降(Vf):600mV@1.0A;")
      (fields (field (name "Manufacturer") "宏迦橙"))
      (libsource (lib "easyedapro") (part "B5819WS_C7420331"))
    )
    (comp (ref "D9")
      (value "B5819WS")
      (footprint "easyedapro:SOD-323_L1.7-W1.3-LS2.5-FD")
      (description "二极管配置:独立式;直流反向耐压(Vr):40V;平均整流电流(Io):1A;正向压降(Vf):600mV@1.0A;")
      (fields (field (name "Manufacturer") "宏迦橙"))
      (libsource (lib "easyedapro") (part "B5819WS_C7420331"))
    )
    (comp (ref "Q7")
      (value "TPH1R403NL")
      (footprint "easyedapro:DSOP-8_L5.0-W5.0-P1.27-LS6.0-BL-EP")
      (fields (field (name "Manufacturer") "TOSHIBA(东芝)"))
      (libsource (lib "easyedapro") (part "TPH1R403NL"))
    )
    (comp (ref "Q8")
      (value "TPH1R403NL")
      (footprint "easyedapro:DSOP-8_L5.0-W5.0-P1.27-LS6.0-BL-EP")
      (fields (field (name "Manufacturer") "TOSHIBA(东芝)"))
      (libsource (lib "easyedapro") (part "TPH1R403NL"))
    )
    (comp (ref "Q9")
      (value "TPH1R403NL")
      (footprint "easyedapro:DSOP-8_L5.0-W5.0-P1.27-LS6.0-BL-EP")
      (fields (field (name "Manufacturer") "TOSHIBA(东芝)"))
      (libsource (lib "easyedapro") (part "TPH1R403NL"))
    )
    (comp (ref "Q10")
      (value "TPH1R403NL")
      (footprint "easyedapro:DSOP-8_L5.0-W5.0-P1.27-LS6.0-BL-EP")
      (fields (field (name "Manufacturer") "TOSHIBA(东芝)"))
      (libsource (lib "easyedapro") (part "TPH1R403NL"))
    )
    (comp (ref "Q11")
      (value "TPH1R403NL")
      (footprint "easyedapro:DSOP-8_L5.0-W5.0-P1.27-LS6.0-BL-EP")
      (fields (field (name "Manufacturer") "TOSHIBA(东芝)"))
      (libsource (lib "easyedapro") (part "TPH1R403NL"))
    )
    (comp (ref "Q12")
      (value "TPH1R403NL")
      (footprint "easyedapro:DSOP-8_L5.0-W5.0-P1.27-LS6.0-BL-EP")
      (fields (field (name "Manufacturer") "TOSHIBA(东芝)"))
      (libsource (lib "easyedapro") (part "TPH1R403NL"))
    )
    (comp (ref "R35")
      (value "100R")
      (footprint "easyedapro:R0603")
      (libsource (lib "easyedapro") (part "电阻"))
    )
    (comp (ref "R36")
      (value "4.7R")
      (footprint "easyedapro:R0603")
      (libsource (lib "easyedapro") (part "电阻"))
    )
    (comp (ref "R37")
      (value "4.7R")
      (footprint "easyedapro:R0603")
      (libsource (lib "easyedapro") (part "电阻"))
    )
    (comp (ref "R38")
      (value "4.7R")
      (footprint "easyedapro:R0603")
      (libsource (lib "easyedapro") (part "电阻"))
    )
    (comp (ref "R39")
      (value "4.7R")
      (footprint "easyedapro:R0603")
      (libsource (lib "easyedapro") (part "电阻"))
    )
    (comp (ref "R40")
      (value "4.7R")
      (footprint "easyedapro:R0603")
      (libsource (lib "easyedapro") (part "电阻"))
    )
    (comp (ref "R41")
      (value "4.7R")
      (footprint "easyedapro:R0603")
      (libsource (lib "easyedapro") (part "电阻"))
    )
    (comp (ref "U28")
      (value "FD6288Q")
      (footprint "easyedapro:QFN-24_L4.0-W4.0-P0.50-BL-EP2.6")
      (fields (field (name "Manufacturer") "Fortior Tech(峰岹)"))
      (libsource (lib "easyedapro") (part "FD6288Q_C328453"))
    )
  )
  (nets
    (net (code "1") (name "ABMF1") (class "Default")
      (node (ref "R2") (pin "1") (pinfunction "1_1") (pintype "input"))
      (node (ref "R3") (pin "1") (pinfunction "1_1") (pintype "input"))
      (node (ref "R8") (pin "2") (pinfunction "2_2") (pintype "input"))
      (node (ref "U15") (pin "28") (pinfunction "CMP+/TXD_2/INT3/P3.7_28") (pintype "unspecified"))
    )
    (net (code "2") (name "ABMF2") (class "Default")
      (node (ref "R22") (pin "1") (pinfunction "1_1") (pintype "input"))
      (node (ref "R23") (pin "1") (pinfunction "1_1") (pintype "input"))
      (node (ref "R28") (pin "2") (pinfunction "2_2") (pintype "input"))
      (node (ref "U22") (pin "28") (pinfunction "CMP+/TXD_2/INT3/P3.7_28") (pintype "unspecified"))
    )
    (net (code "3") (name "BATADC1") (class "Default")
      (node (ref "C5") (pin "2") (pinfunction "2_2") (pintype "input"))
      (node (ref "R11") (pin "1") (pinfunction "1_1") (pintype "input"))
      (node (ref "R12") (pin "2") (pinfunction "2_2") (pintype "input"))
      (node (ref "U15") (pin "46") (pinfunction "LINTX/CAN2_TX/PWM8_3/TXD4/ADC11/AD3/P0.3_46") (pintype "unspecified"))
    )
    (net (code "4") (name "BATADC2") (class "Default")
      (node (ref "C23") (pin "2") (pinfunction "2_2") (pintype "input"))
      (node (ref "R31") (pin "1") (pinfunction "1_1") (pintype "input"))
      (node (ref "R32") (pin "2") (pinfunction "2_2") (pintype "input"))
      (node (ref "U22") (pin "46") (pinfunction "LINTX/CAN2_TX/PWM8_3/TXD4/ADC11/AD3/P0.3_46") (pintype "unspecified"))
    )
    (net (code "5") (name "BBMF1") (class "Default")
      (node (ref "R4") (pin "1") (pinfunction "1_1") (pintype "input"))
      (node (ref "R5") (pin "1") (pinfunction "1_1") (pintype "input"))
      (node (ref "R9") (pin "2") (pinfunction "2_2") (pintype "input"))
      (node (ref "U15") (pin "25") (pinfunction "CAN_TX_2/CMP+_3/TXD3_2/P5.1_25") (pintype "unspecified"))
    )
    (net (code "6") (name "BBMF2") (class "Default")
      (node (ref "R24") (pin "1") (pinfunction "1_1") (pintype "input"))
      (node (ref "R25") (pin "1") (pinfunction "1_1") (pintype "input"))
      (node (ref "R29") (pin "2") (pinfunction "2_2") (pintype "input"))
      (node (ref "U22") (pin "25") (pinfunction "CAN_TX_2/CMP+_3/TXD3_2/P5.1_25") (pintype "unspecified"))
    )
    (net (code "7") (name "CBMF1") (class "Default")
      (node (ref "R10") (pin "2") (pinfunction "2_2") (pintype "input"))
      (node (ref "R6") (pin "1") (pinfunction "1_1") (pintype "input"))
      (node (ref "R7") (pin "1") (pinfunction "1_1") (pintype "input"))
      (node (ref "U15") (pin "24") (pinfunction "P5.0/RXD3_2/CMP+_2/CAN_RX_2_24") (pintype "unspecified"))
    )
    (net (code "8") (name "CBMF2") (class "Default")
      (node (ref "R26") (pin "1") (pinfunction "1_1") (pintype "input"))
      (node (ref "R27") (pin "1") (pinfunction "1_1") (pintype "input"))
      (node (ref "R30") (pin "2") (pinfunction "2_2") (pintype "input"))
      (node (ref "U22") (pin "24") (pinfunction "P5.0/RXD3_2/CMP+_2/CAN_RX_2_24") (pintype "unspecified"))
    )
    (net (code "9") (name "DOWN") (class "Default")
      (node (ref "D10") (pin "2") (pinfunction "2_2") (pintype "unspecified"))
      (node (ref "R43") (pin "2") (pinfunction "2_2") (pintype "input"))
    )
    (net (code "10") (name "GATE") (class "Default")
      (node (ref "Q13") (pin "1") (pinfunction "G_1") (pintype "input"))
    )
    (net (code "11") (name "GND") (class "Default")
      (node (ref "C1") (pin "2") (pinfunction "2_2") (pintype "input"))
      (node (ref "C10") (pin "1") (pinfunction "1_1") (pintype "input"))
      (node (ref "C11") (pin "1") (pinfunction "1_1") (pintype "input"))
      (node (ref "C12") (pin "1") (pinfunction "1_1") (pintype "input"))
      (node (ref "C13") (pin "1") (pinfunction "1_1") (pintype "input"))
      (node (ref "C14") (pin "1") (pinfunction "1_1") (pintype "input"))
      (node (ref "C15") (pin "2") (pinfunction "2_2") (pintype "input"))
      (node (ref "C19") (pin "2") (pinfunction "2_2") (pintype "input"))
      (node (ref "C2") (pin "1") (pinfunction "1_1") (pintype "input"))
      (node (ref "C20") (pin "1") (pinfunction "1_1") (pintype "input"))
      (node (ref "C21") (pin "1") (pinfunction "1_1") (pintype "input"))
      (node (ref "C22") (pin "2") (pinfunction "2_2") (pintype "input"))
      (node (ref "C23") (pin "1") (pinfunction "1_1") (pintype "input"))
      (node (ref "C24") (pin "1") (pinfunction "1_1") (pintype "input"))
      (node (ref "C25") (pin "1") (pinfunction "1_1") (pintype "input"))
      (node (ref "C26") (pin "1") (pinfunction "1_1") (pintype "input"))
      (node (ref "C27") (pin "1") (pinfunction "1_1") (pintype "input"))
      (node (ref "C28") (pin "1") (pinfunction "1_1") (pintype "input"))
      (node (ref "C29") (pin "1") (pinfunction "1_1") (pintype "input"))
      (node (ref "C3") (pin "1") (pinfunction "1_1") (pintype "input"))
      (node (ref "C33") (pin "2") (pinfunction "2_2") (pintype "input"))
      (node (ref "C37") (pin "1") (pinfunction "1_1") (pintype "input"))
      (node (ref "C4") (pin "2") (pinfunction "2_2") (pintype "input"))
      (node (ref "C5") (pin "1") (pinfunction "1_1") (pintype "input"))
      (node (ref "C6") (pin "1") (pinfunction "1_1") (pintype "input"))
      (node (ref "C7") (pin "1") (pinfunction "1_1") (pintype "input"))
      (node (ref "C8") (pin "1") (pinfunction "1_1") (pintype "input"))
      (node (ref "C9") (pin "1") (pinfunction "1_1") (pintype "input"))
      (node (ref "CN1") (pin "1") (pinfunction "-_1") (pintype "unspecified"))
      (node (ref "CN1") (pin "3") (pinfunction "3_3") (pintype "unspecified"))
      (node (ref "CN1") (pin "4") (pinfunction "4_4") (pintype "unspecified"))
      (node (ref "D1") (pin "2") (pinfunction "A_2") (pintype "unspecified"))
      (node (ref "D6") (pin "2") (pinfunction "A_2") (pintype "unspecified"))
      (node (ref "H1") (pin "4") (pinfunction "4_4") (pintype "unspecified"))
      (node (ref "H3") (pin "4") (pinfunction "4_4") (pintype "unspecified"))
      (node (ref "Q10") (pin "1") (pinfunction "S_1") (pintype "unspecified"))
      (node (ref "Q10") (pin "2") (pinfunction "S_2") (pintype "unspecified"))
      (node (ref "Q10") (pin "3") (pinfunction "S_3") (pintype "unspecified"))
      (node (ref "Q12") (pin "1") (pinfunction "S_1") (pintype "unspecified"))
      (node (ref "Q12") (pin "2") (pinfunction "S_2") (pintype "unspecified"))
      (node (ref "Q12") (pin "3") (pinfunction "S_3") (pintype "unspecified"))
      (node (ref "Q2") (pin "1") (pinfunction "S_1") (pintype "unspecified"))
      (node (ref "Q2") (pin "2") (pinfunction "S_2") (pintype "unspecified"))
      (node (ref "Q2") (pin "3") (pinfunction "S_3") (pintype "unspecified"))
      (node (ref "Q4") (pin "1") (pinfunction "S_1") (pintype "unspecified"))
      (node (ref "Q4") (pin "2") (pinfunction "S_2") (pintype "unspecified"))
      (node (ref "Q4") (pin "3") (pinfunction "S_3") (pintype "unspecified"))
      (node (ref "Q6") (pin "1") (pinfunction "S_1") (pintype "unspecified"))
      (node (ref "Q6") (pin "2") (pinfunction "S_2") (pintype "unspecified"))
      (node (ref "Q6") (pin "3") (pinfunction "S_3") (pintype "unspecified"))
      (node (ref "Q8") (pin "1") (pinfunction "S_1") (pintype "unspecified"))
      (node (ref "Q8") (pin "2") (pinfunction "S_2") (pintype "unspecified"))
      (node (ref "Q8") (pin "3") (pinfunction "S_3") (pintype "unspecified"))
      (node (ref "R10") (pin "1") (pinfunction "1_1") (pintype "input"))
      (node (ref "R12") (pin "1") (pinfunction "1_1") (pintype "input"))
      (node (ref "R28") (pin "1") (pinfunction "1_1") (pintype "input"))
      (node (ref "R29") (pin "1") (pinfunction "1_1") (pintype "input"))
      (node (ref "R30") (pin "1") (pinfunction "1_1") (pintype "input"))
      (node (ref "R32") (pin "1") (pinfunction "1_1") (pintype "input"))
      (node (ref "R43") (pin "1") (pinfunction "1_1") (pintype "input"))
      (node (ref "R8") (pin "1") (pinfunction "1_1") (pintype "input"))
      (node (ref "R9") (pin "1") (pinfunction "1_1") (pintype "input"))
      (node (ref "U15") (pin "17") (pinfunction "GND/AGND/Vref-_17") (pintype "unspecified"))
      (node (ref "U16") (pin "1") (pinfunction "GND_1") (pintype "unspecified"))
      (node (ref "U17") (pin "25") (pinfunction "EP_25") (pintype "unspecified"))
      (node (ref "U17") (pin "6") (pinfunction "COM_6") (pintype "unspecified"))
      (node (ref "U18") (pin "1") (pinfunction "1_1") (pintype "input"))
      (node (ref "U19") (pin "1") (pinfunction "1_1") (pintype "input"))
      (node (ref "U22") (pin "17") (pinfunction "GND/AGND/Vref-_17") (pintype "unspecified"))
      (node (ref "U28") (pin "25") (pinfunction "EP_25") (pintype "unspecified"))
      (node (ref "U28") (pin "6") (pinfunction "COM_6") (pintype "unspecified"))
    )
    (net (code "12") (name "HOA1") (class "Default")
      (node (ref "R16") (pin "1") (pinfunction "1_1") (pintype "input"))
      (node (ref "U17") (pin "19") (pinfunction "HO1_19") (pintype "unspecified"))
    )
    (net (code "13") (name "HOA2") (class "Default")
      (node (ref "R36") (pin "1") (pinfunction "1_1") (pintype "input"))
      (node (ref "U28") (pin "19") (pinfunction "HO1_19") (pintype "unspecified"))
    )
    (net (code "14") (name "HOB1") (class "Default")
      (node (ref "R18") (pin "1") (pinfunction "1_1") (pintype "input"))
      (node (ref "U17") (pin "16") (pinfunction "HO2_16") (pintype "unspecified"))
    )
    (net (code "15") (name "HOB2") (class "Default")
      (node (ref "R38") (pin "1") (pinfunction "1_1") (pintype "input"))
      (node (ref "U28") (pin "16") (pinfunction "HO2_16") (pintype "unspecified"))
    )
    (net (code "16") (name "HOC1") (class "Default")
      (node (ref "R20") (pin "1") (pinfunction "1_1") (pintype "input"))
      (node (ref "U17") (pin "13") (pinfunction "HO3_13") (pintype "unspecified"))
    )
    (net (code "17") (name "HOC2") (class "Default")
      (node (ref "R40") (pin "1") (pinfunction "1_1") (pintype "input"))
      (node (ref "U28") (pin "13") (pinfunction "HO3_13") (pintype "unspecified"))
    )
    (net (code "18") (name "LED1") (class "Default")
      (node (ref "R14") (pin "2") (pinfunction "2_2") (pintype "input"))
      (node (ref "U15") (pin "32") (pinfunction "TXD_4/RD/P4.4_32") (pintype "unspecified"))
    )
    (net (code "19") (name "LED2") (class "Default")
      (node (ref "R34") (pin "2") (pinfunction "2_2") (pintype "input"))
      (node (ref "U22") (pin "32") (pinfunction "TXD_4/RD/P4.4_32") (pintype "unspecified"))
    )
    (net (code "20") (name "LOA1") (class "Default")
      (node (ref "R17") (pin "1") (pinfunction "1_1") (pintype "input"))
      (node (ref "U17") (pin "11") (pinfunction "LO1_11") (pintype "unspecified"))
    )
    (net (code "21") (name "LOA2") (class "Default")
      (node (ref "R37") (pin "1") (pinfunction "1_1") (pintype "input"))
      (node (ref "U28") (pin "11") (pinfunction "LO1_11") (pintype "unspecified"))
    )
    (net (code "22") (name "LOB1") (class "Default")
      (node (ref "R19") (pin "1") (pinfunction "1_1") (pintype "input"))
      (node (ref "U17") (pin "10") (pinfunction "LO2_10") (pintype "unspecified"))
    )
    (net (code "23") (name "LOB2") (class "Default")
      (node (ref "R39") (pin "1") (pinfunction "1_1") (pintype "input"))
      (node (ref "U28") (pin "10") (pinfunction "LO2_10") (pintype "unspecified"))
    )
    (net (code "24") (name "LOC1") (class "Default")
      (node (ref "R21") (pin "1") (pinfunction "1_1") (pintype "input"))
      (node (ref "U17") (pin "9") (pinfunction "LO3_9") (pintype "unspecified"))
    )
    (net (code "25") (name "LOC2") (class "Default")
      (node (ref "R41") (pin "1") (pinfunction "1_1") (pintype "input"))
      (node (ref "U28") (pin "9") (pinfunction "LO3_9") (pintype "unspecified"))
    )
    (net (code "26") (name "MID1") (class "Default")
      (node (ref "R3") (pin "2") (pinfunction "2_2") (pintype "input"))
      (node (ref "R5") (pin "2") (pinfunction "2_2") (pintype "input"))
      (node (ref "R7") (pin "2") (pinfunction "2_2") (pintype "input"))
      (node (ref "U15") (pin "27") (pinfunction "CMP-/RXD_2/INT2/P3.6_27") (pintype "unspecified"))
    )
    (net (code "27") (name "MID2") (class "Default")
      (node (ref "R23") (pin "2") (pinfunction "2_2") (pintype "input"))
      (node (ref "R25") (pin "2") (pinfunction "2_2") (pintype "input"))
      (node (ref "R27") (pin "2") (pinfunction "2_2") (pintype "input"))
      (node (ref "U22") (pin "27") (pinfunction "CMP-/RXD_2/INT2/P3.6_27") (pintype "unspecified"))
    )
    (net (code "28") (name "Net-(D1-K)") (class "Default")
      (node (ref "C15") (pin "1") (pinfunction "1_1") (pintype "input"))
      (node (ref "D1") (pin "1") (pinfunction "K_1") (pintype "unspecified"))
      (node (ref "D2") (pin "1") (pinfunction "A_1") (pintype "unspecified"))
      (node (ref "D3") (pin "1") (pinfunction "A_1") (pintype "unspecified"))
      (node (ref "D4") (pin "1") (pinfunction "A_1") (pintype "unspecified"))
      (node (ref "R15") (pin "2") (pinfunction "2_2") (pintype "input"))
      (node (ref "U17") (pin "4") (pinfunction "VCC_4") (pintype "unspecified"))
    )
    (net (code "29") (name "Net-(D5-K)") (class "Default")
      (node (ref "D5") (pin "1") (pinfunction "K_1") (pintype "unspecified"))
      (node (ref "U16") (pin "2") (pinfunction "VIN_2") (pintype "unspecified"))
    )
    (net (code "30") (name "Net-(D6-K)") (class "Default")
      (node (ref "C33") (pin "1") (pinfunction "1_1") (pintype "input"))
      (node (ref "D6") (pin "1") (pinfunction "K_1") (pintype "unspecified"))
      (node (ref "D7") (pin "1") (pinfunction "A_1") (pintype "unspecified"))
      (node (ref "D8") (pin "1") (pinfunction "A_1") (pintype "unspecified"))
      (node (ref "D9") (pin "1") (pinfunction "A_1") (pintype "unspecified"))
      (node (ref "R35") (pin "2") (pinfunction "2_2") (pintype "input"))
      (node (ref "U28") (pin "4") (pinfunction "VCC_4") (pintype "unspecified"))
    )
    (net (code "31") (name "Net-(H1-Pad6)") (class "Default")
      (node (ref "H1") (pin "6") (pinfunction "6_6") (pintype "unspecified"))
      (node (ref "R13") (pin "2") (pinfunction "2_2") (pintype "input"))
    )
    (net (code "32") (name "Net-(H3-Pad6)") (class "Default")
      (node (ref "H3") (pin "6") (pinfunction "6_6") (pintype "unspecified"))
      (node (ref "R42") (pin "2") (pinfunction "2_2") (pintype "input"))
    )
    (net (code "33") (name "Net-(LED1-C)") (class "Default")
      (node (ref "LED1") (pin "1") (pinfunction "C_1") (pintype "input"))
      (node (ref "R14") (pin "1") (pinfunction "1_1") (pintype "input"))
    )
    (net (code "34") (name "Net-(LED2-C)") (class "Default")
      (node (ref "LED2") (pin "1") (pinfunction "C_1") (pintype "input"))
      (node (ref "R34") (pin "1") (pinfunction "1_1") (pintype "input"))
    )
    (net (code "35") (name "Net-(Q1-G)") (class "Default")
      (node (ref "Q1") (pin "4") (pinfunction "G_4") (pintype "unspecified"))
      (node (ref "R16") (pin "2") (pinfunction "2_2") (pintype "input"))
    )
    (net (code "36") (name "Net-(Q2-G)") (class "Default")
      (node (ref "Q2") (pin "4") (pinfunction "G_4") (pintype "unspecified"))
      (node (ref "R17") (pin "2") (pinfunction "2_2") (pintype "input"))
    )
    (net (code "37") (name "Net-(Q3-G)") (class "Default")
      (node (ref "Q3") (pin "4") (pinfunction "G_4") (pintype "unspecified"))
      (node (ref "R18") (pin "2") (pinfunction "2_2") (pintype "input"))
    )
    (net (code "38") (name "Net-(Q4-G)") (class "Default")
      (node (ref "Q4") (pin "4") (pinfunction "G_4") (pintype "unspecified"))
      (node (ref "R19") (pin "2") (pinfunction "2_2") (pintype "input"))
    )
    (net (code "39") (name "Net-(Q5-G)") (class "Default")
      (node (ref "Q5") (pin "4") (pinfunction "G_4") (pintype "unspecified"))
      (node (ref "R20") (pin "2") (pinfunction "2_2") (pintype "input"))
    )
    (net (code "40") (name "Net-(Q6-G)") (class "Default")
      (node (ref "Q6") (pin "4") (pinfunction "G_4") (pintype "unspecified"))
      (node (ref "R21") (pin "2") (pinfunction "2_2") (pintype "input"))
    )
    (net (code "41") (name "Net-(Q7-G)") (class "Default")
      (node (ref "Q7") (pin "4") (pinfunction "G_4") (pintype "unspecified"))
      (node (ref "R36") (pin "2") (pinfunction "2_2") (pintype "input"))
    )
    (net (code "42") (name "Net-(Q8-G)") (class "Default")
      (node (ref "Q8") (pin "4") (pinfunction "G_4") (pintype "unspecified"))
      (node (ref "R37") (pin "2") (pinfunction "2_2") (pintype "input"))
    )
    (net (code "43") (name "Net-(Q9-G)") (class "Default")
      (node (ref "Q9") (pin "4") (pinfunction "G_4") (pintype "unspecified"))
      (node (ref "R38") (pin "2") (pinfunction "2_2") (pintype "input"))
    )
    (net (code "44") (name "Net-(Q10-G)") (class "Default")
      (node (ref "Q10") (pin "4") (pinfunction "G_4") (pintype "unspecified"))
      (node (ref "R39") (pin "2") (pinfunction "2_2") (pintype "input"))
    )
    (net (code "45") (name "Net-(Q11-G)") (class "Default")
      (node (ref "Q11") (pin "4") (pinfunction "G_4") (pintype "unspecified"))
      (node (ref "R40") (pin "2") (pinfunction "2_2") (pintype "input"))
    )
    (net (code "46") (name "Net-(Q12-G)") (class "Default")
      (node (ref "Q12") (pin "4") (pinfunction "G_4") (pintype "unspecified"))
      (node (ref "R41") (pin "2") (pinfunction "2_2") (pintype "input"))
    )
    (net (code "47") (name "Net-(U15-UCAP)") (class "Default")
      (node (ref "C1") (pin "1") (pinfunction "1_1") (pintype "input"))
      (node (ref "U15") (pin "13") (pinfunction "UCAP_13") (pintype "unspecified"))
    )
    (net (code "48") (name "Net-(U15-Vref)") (class "Default")
      (node (ref "C4") (pin "1") (pinfunction "1_1") (pintype "input"))
      (node (ref "L1") (pin "2") (pinfunction "2_2") (pintype "unspecified"))
      (node (ref "U15") (pin "16") (pinfunction "Vref_16") (pintype "unspecified"))
    )
    (net (code "49") (name "Net-(U22-UCAP)") (class "Default")
      (node (ref "C19") (pin "1") (pinfunction "1_1") (pintype "input"))
      (node (ref "U22") (pin "13") (pinfunction "UCAP_13") (pintype "unspecified"))
    )
    (net (code "50") (name "Net-(U22-Vref)") (class "Default")
      (node (ref "C22") (pin "1") (pinfunction "1_1") (pintype "input"))
      (node (ref "L2") (pin "2") (pinfunction "2_2") (pintype "unspecified"))
      (node (ref "U22") (pin "16") (pinfunction "Vref_16") (pintype "unspecified"))
    )
    (net (code "51") (name "PWMAH1") (class "Default")
      (node (ref "U15") (pin "33") (pinfunction "PWM5/PWM1P_2/A8/P2.0_33") (pintype "unspecified"))
      (node (ref "U17") (pin "22") (pinfunction "HIN1_22") (pintype "unspecified"))
    )
    (net (code "52") (name "PWMAH2") (class "Default")
      (node (ref "U22") (pin "33") (pinfunction "PWM5/PWM1P_2/A8/P2.0_33") (pintype "unspecified"))
      (node (ref "U28") (pin "22") (pinfunction "HIN1_22") (pintype "unspecified"))
    )
    (net (code "53") (name "PWMAL1") (class "Default")
      (node (ref "U15") (pin "34") (pinfunction "PWM6/PWM1N_2/A9/P2.1_34") (pintype "unspecified"))
      (node (ref "U17") (pin "1") (pinfunction "LIN1_1") (pintype "unspecified"))
    )
    (net (code "54") (name "PWMAL2") (class "Default")
      (node (ref "U22") (pin "34") (pinfunction "PWM6/PWM1N_2/A9/P2.1_34") (pintype "unspecified"))
      (node (ref "U28") (pin "1") (pinfunction "LIN1_1") (pintype "unspecified"))
    )
    (net (code "55") (name "PWMBH1") (class "Default")
      (node (ref "U15") (pin "35") (pinfunction "PWM7/PWM2P_2/S2SS_2/S1SS_2/SS_2/A10/P2.2_35") (pintype "unspecified"))
      (node (ref "U17") (pin "23") (pinfunction "HIN2_23") (pintype "unspecified"))
    )
    (net (code "56") (name "PWMBH2") (class "Default")
      (node (ref "U22") (pin "35") (pinfunction "PWM7/PWM2P_2/S2SS_2/S1SS_2/SS_2/A10/P2.2_35") (pintype "unspecified"))
      (node (ref "U28") (pin "23") (pinfunction "HIN2_23") (pintype "unspecified"))
    )
    (net (code "57") (name "PWMBL1") (class "Default")
      (node (ref "U15") (pin "36") (pinfunction "PWM8/PWM2N_2/S2MOSI_2/S1MOSI_2/MOSI_2/A11/P2.3_36") (pintype "unspecified"))
      (node (ref "U17") (pin "2") (pinfunction "LIN2_2") (pintype "unspecified"))
    )
    (net (code "58") (name "PWMBL2") (class "Default")
      (node (ref "U22") (pin "36") (pinfunction "PWM8/PWM2N_2/S2MOSI_2/S1MOSI_2/MOSI_2/A11/P2.3_36") (pintype "unspecified"))
      (node (ref "U28") (pin "2") (pinfunction "LIN2_2") (pintype "unspecified"))
    )
    (net (code "59") (name "PWMCH1") (class "Default")
      (node (ref "U15") (pin "37") (pinfunction "PWM3P_2/SDA_2/S2MISO_2/S1MISO_2/MISO_2/A12/P2.4_37") (pintype "unspecified"))
      (node (ref "U17") (pin "24") (pinfunction "HIN3_24") (pintype "unspecified"))
    )
    (net (code "60") (name "PWMCH2") (class "Default")
      (node (ref "U22") (pin "37") (pinfunction "PWM3P_2/SDA_2/S2MISO_2/S1MISO_2/MISO_2/A12/P2.4_37") (pintype "unspecified"))
      (node (ref "U28") (pin "24") (pinfunction "HIN3_24") (pintype "unspecified"))
    )
    (net (code "61") (name "PWMCL1") (class "Default")
      (node (ref "U15") (pin "38") (pinfunction "PWM3N_2/SCL_2/S2SCLK_2/S1SCLK_2/SCLK_2/A13/P2.5_38") (pintype "unspecified"))
      (node (ref "U17") (pin "3") (pinfunction "LIN3_3") (pintype "unspecified"))
    )
    (net (code "62") (name "PWMCL2") (class "Default")
      (node (ref "U22") (pin "38") (pinfunction "PWM3N_2/SCL_2/S2SCLK_2/S1SCLK_2/SCLK_2/A13/P2.5_38") (pintype "unspecified"))
      (node (ref "U28") (pin "3") (pinfunction "LIN3_3") (pintype "unspecified"))
    )
    (net (code "63") (name "PWMIN1") (class "Default")
      (node (ref "R13") (pin "1") (pinfunction "1_1") (pintype "input"))
      (node (ref "U15") (pin "43") (pinfunction "CAN_RX/PWM5_3/RXD3/ADC8/AD0/P0.0_43") (pintype "unspecified"))
    )
    (net (code "64") (name "PWMIN2") (class "Default")
      (node (ref "R42") (pin "1") (pinfunction "1_1") (pintype "input"))
      (node (ref "U22") (pin "43") (pinfunction "CAN_RX/PWM5_3/RXD3/ADC8/AD0/P0.0_43") (pintype "unspecified"))
    )
    (net (code "65") (name "RX1") (class "Default")
      (node (ref "H1") (pin "2") (pinfunction "2_2") (pintype "unspecified"))
      (node (ref "U15") (pin "19") (pinfunction "P3.0/D-/RXD/INT4_19") (pintype "unspecified"))
    )
    (net (code "66") (name "RX2") (class "Default")
      (node (ref "H3") (pin "2") (pinfunction "2_2") (pintype "unspecified"))
      (node (ref "U22") (pin "19") (pinfunction "P3.0/D-/RXD/INT4_19") (pintype "unspecified"))
    )
    (net (code "67") (name "TX1") (class "Default")
      (node (ref "H1") (pin "3") (pinfunction "3_3") (pintype "unspecified"))
      (node (ref "U15") (pin "20") (pinfunction "P3.1/D+/TXD_20") (pintype "unspecified"))
    )
    (net (code "68") (name "TX2") (class "Default")
      (node (ref "H3") (pin "3") (pinfunction "3_3") (pintype "unspecified"))
      (node (ref "U22") (pin "20") (pinfunction "P3.1/D+/TXD_20") (pintype "unspecified"))
    )
    (net (code "69") (name "VBA1") (class "Default")
      (node (ref "C16") (pin "1") (pinfunction "1_1") (pintype "input"))
      (node (ref "D2") (pin "2") (pinfunction "K_2") (pintype "unspecified"))
      (node (ref "U17") (pin "20") (pinfunction "VB1_20") (pintype "unspecified"))
    )
    (net (code "70") (name "VBA2") (class "Default")
      (node (ref "C34") (pin "1") (pinfunction "1_1") (pintype "input"))
      (node (ref "D7") (pin "2") (pinfunction "K_2") (pintype "unspecified"))
      (node (ref "U28") (pin "20") (pinfunction "VB1_20") (pintype "unspecified"))
    )
    (net (code "71") (name "VBAT") (class "Default")
      (node (ref "C10") (pin "2") (pinfunction "2_2") (pintype "input"))
      (node (ref "C11") (pin "2") (pinfunction "2_2") (pintype "input"))
      (node (ref "C24") (pin "2") (pinfunction "2_2") (pintype "input"))
      (node (ref "C25") (pin "2") (pinfunction "2_2") (pintype "input"))
      (node (ref "C26") (pin "2") (pinfunction "2_2") (pintype "input"))
      (node (ref "C27") (pin "2") (pinfunction "2_2") (pintype "input"))
      (node (ref "C28") (pin "2") (pinfunction "2_2") (pintype "input"))
      (node (ref "C29") (pin "2") (pinfunction "2_2") (pintype "input"))
      (node (ref "C6") (pin "2") (pinfunction "2_2") (pintype "input"))
      (node (ref "C7") (pin "2") (pinfunction "2_2") (pintype "input"))
      (node (ref "C8") (pin "2") (pinfunction "2_2") (pintype "input"))
      (node (ref "C9") (pin "2") (pinfunction "2_2") (pintype "input"))
      (node (ref "CN1") (pin "2") (pinfunction "+_2") (pintype "unspecified"))
      (node (ref "D10") (pin "1") (pinfunction "1_1") (pintype "unspecified"))
      (node (ref "Q1") (pin "5") (pinfunction "D_5") (pintype "unspecified"))
      (node (ref "Q1") (pin "6") (pinfunction "D_6") (pintype "unspecified"))
      (node (ref "Q1") (pin "7") (pinfunction "D_7") (pintype "unspecified"))
      (node (ref "Q1") (pin "8") (pinfunction "D_8") (pintype "unspecified"))
      (node (ref "Q1") (pin "9") (pinfunction "D_9") (pintype "unspecified"))
      (node (ref "Q11") (pin "5") (pinfunction "D_5") (pintype "unspecified"))
      (node (ref "Q11") (pin "6") (pinfunction "D_6") (pintype "unspecified"))
      (node (ref "Q11") (pin "7") (pinfunction "D_7") (pintype "unspecified"))
      (node (ref "Q11") (pin "8") (pinfunction "D_8") (pintype "unspecified"))
      (node (ref "Q11") (pin "9") (pinfunction "D_9") (pintype "unspecified"))
      (node (ref "Q13") (pin "2") (pinfunction "S_2") (pintype "input"))
      (node (ref "Q3") (pin "5") (pinfunction "D_5") (pintype "unspecified"))
      (node (ref "Q3") (pin "6") (pinfunction "D_6") (pintype "unspecified"))
      (node (ref "Q3") (pin "7") (pinfunction "D_7") (pintype "unspecified"))
      (node (ref "Q3") (pin "8") (pinfunction "D_8") (pintype "unspecified"))
      (node (ref "Q3") (pin "9") (pinfunction "D_9") (pintype "unspecified"))
      (node (ref "Q5") (pin "5") (pinfunction "D_5") (pintype "unspecified"))
      (node (ref "Q5") (pin "6") (pinfunction "D_6") (pintype "unspecified"))
      (node (ref "Q5") (pin "7") (pinfunction "D_7") (pintype "unspecified"))
      (node (ref "Q5") (pin "8") (pinfunction "D_8") (pintype "unspecified"))
      (node (ref "Q5") (pin "9") (pinfunction "D_9") (pintype "unspecified"))
      (node (ref "Q7") (pin "5") (pinfunction "D_5") (pintype "unspecified"))
      (node (ref "Q7") (pin "6") (pinfunction "D_6") (pintype "unspecified"))
      (node (ref "Q7") (pin "7") (pinfunction "D_7") (pintype "unspecified"))
      (node (ref "Q7") (pin "8") (pinfunction "D_8") (pintype "unspecified"))
      (node (ref "Q7") (pin "9") (pinfunction "D_9") (pintype "unspecified"))
      (node (ref "Q9") (pin "5") (pinfunction "D_5") (pintype "unspecified"))
      (node (ref "Q9") (pin "6") (pinfunction "D_6") (pintype "unspecified"))
      (node (ref "Q9") (pin "7") (pinfunction "D_7") (pintype "unspecified"))
      (node (ref "Q9") (pin "8") (pinfunction "D_8") (pintype "unspecified"))
      (node (ref "Q9") (pin "9") (pinfunction "D_9") (pintype "unspecified"))
      (node (ref "R11") (pin "2") (pinfunction "2_2") (pintype "input"))
      (node (ref "R15") (pin "1") (pinfunction "1_1") (pintype "input"))
      (node (ref "R31") (pin "2") (pinfunction "2_2") (pintype "input"))
      (node (ref "R35") (pin "1") (pinfunction "1_1") (pintype "input"))
    )
    (net (code "72") (name "VBB1") (class "Default")
      (node (ref "C17") (pin "1") (pinfunction "1_1") (pintype "input"))
      (node (ref "D3") (pin "2") (pinfunction "K_2") (pintype "unspecified"))
      (node (ref "U17") (pin "17") (pinfunction "VB2_17") (pintype "unspecified"))
    )
    (net (code "73") (name "VBB2") (class "Default")
      (node (ref "C35") (pin "1") (pinfunction "1_1") (pintype "input"))
      (node (ref "D8") (pin "2") (pinfunction "K_2") (pintype "unspecified"))
      (node (ref "U28") (pin "17") (pinfunction "VB2_17") (pintype "unspecified"))
    )
    (net (code "74") (name "VBC1") (class "Default")
      (node (ref "C18") (pin "1") (pinfunction "1_1") (pintype "input"))
      (node (ref "D4") (pin "2") (pinfunction "K_2") (pintype "unspecified"))
      (node (ref "U17") (pin "14") (pinfunction "VB3_14") (pintype "unspecified"))
    )
    (net (code "75") (name "VBC2") (class "Default")
      (node (ref "C36") (pin "1") (pinfunction "1_1") (pintype "input"))
      (node (ref "D9") (pin "2") (pinfunction "K_2") (pintype "unspecified"))
      (node (ref "U28") (pin "14") (pinfunction "VB3_14") (pintype "unspecified"))
    )
    (net (code "76") (name "VCC5V") (class "Default")
      (node (ref "C13") (pin "2") (pinfunction "2_2") (pintype "input"))
      (node (ref "C14") (pin "2") (pinfunction "2_2") (pintype "input"))
      (node (ref "C2") (pin "2") (pinfunction "2_2") (pintype "input"))
      (node (ref "C20") (pin "2") (pinfunction "2_2") (pintype "input"))
      (node (ref "C21") (pin "2") (pinfunction "2_2") (pintype "input"))
      (node (ref "C3") (pin "2") (pinfunction "2_2") (pintype "input"))
      (node (ref "C37") (pin "2") (pinfunction "2_2") (pintype "input"))
      (node (ref "H1") (pin "1") (pinfunction "1_1") (pintype "unspecified"))
      (node (ref "H1") (pin "5") (pinfunction "5_5") (pintype "unspecified"))
      (node (ref "H3") (pin "1") (pinfunction "1_1") (pintype "unspecified"))
      (node (ref "H3") (pin "5") (pinfunction "5_5") (pintype "unspecified"))
      (node (ref "L1") (pin "1") (pinfunction "1_1") (pintype "unspecified"))
      (node (ref "L2") (pin "1") (pinfunction "1_1") (pintype "unspecified"))
      (node (ref "LED1") (pin "2") (pinfunction "A_2") (pintype "input"))
      (node (ref "LED2") (pin "2") (pinfunction "A_2") (pintype "input"))
      (node (ref "U15") (pin "15") (pinfunction "VCC/AVCC_15") (pintype "unspecified"))
      (node (ref "U16") (pin "3") (pinfunction "VOUT_3") (pintype "unspecified"))
      (node (ref "U22") (pin "15") (pinfunction "VCC/AVCC_15") (pintype "unspecified"))
    )
    (net (code "77") (name "VCC12V") (class "Default")
      (node (ref "C12") (pin "2") (pinfunction "2_2") (pintype "input"))
      (node (ref "D5") (pin "2") (pinfunction "A_2") (pintype "unspecified"))
      (node (ref "Q13") (pin "3") (pinfunction "D_3") (pintype "input"))
    )
    (net (code "78") (name "VSA1") (class "Default")
      (node (ref "C16") (pin "2") (pinfunction "2_2") (pintype "input"))
      (node (ref "Q1") (pin "1") (pinfunction "S_1") (pintype "unspecified"))
      (node (ref "Q1") (pin "2") (pinfunction "S_2") (pintype "unspecified"))
      (node (ref "Q1") (pin "3") (pinfunction "S_3") (pintype "unspecified"))
      (node (ref "Q2") (pin "5") (pinfunction "D_5") (pintype "unspecified"))
      (node (ref "Q2") (pin "6") (pinfunction "D_6") (pintype "unspecified"))
      (node (ref "Q2") (pin "7") (pinfunction "D_7") (pintype "unspecified"))
      (node (ref "Q2") (pin "8") (pinfunction "D_8") (pintype "unspecified"))
      (node (ref "Q2") (pin "9") (pinfunction "D_9") (pintype "unspecified"))
      (node (ref "R2") (pin "2") (pinfunction "2_2") (pintype "input"))
      (node (ref "U17") (pin "18") (pinfunction "VS1_18") (pintype "unspecified"))
    )
    (net (code "79") (name "VSA2") (class "Default")
      (node (ref "C34") (pin "2") (pinfunction "2_2") (pintype "input"))
      (node (ref "Q7") (pin "1") (pinfunction "S_1") (pintype "unspecified"))
      (node (ref "Q7") (pin "2") (pinfunction "S_2") (pintype "unspecified"))
      (node (ref "Q7") (pin "3") (pinfunction "S_3") (pintype "unspecified"))
      (node (ref "Q8") (pin "5") (pinfunction "D_5") (pintype "unspecified"))
      (node (ref "Q8") (pin "6") (pinfunction "D_6") (pintype "unspecified"))
      (node (ref "Q8") (pin "7") (pinfunction "D_7") (pintype "unspecified"))
      (node (ref "Q8") (pin "8") (pinfunction "D_8") (pintype "unspecified"))
      (node (ref "Q8") (pin "9") (pinfunction "D_9") (pintype "unspecified"))
      (node (ref "R22") (pin "2") (pinfunction "2_2") (pintype "input"))
      (node (ref "U28") (pin "18") (pinfunction "VS1_18") (pintype "unspecified"))
    )
    (net (code "80") (name "VSB1") (class "Default")
      (node (ref "C17") (pin "2") (pinfunction "2_2") (pintype "input"))
      (node (ref "Q3") (pin "1") (pinfunction "S_1") (pintype "unspecified"))
      (node (ref "Q3") (pin "2") (pinfunction "S_2") (pintype "unspecified"))
      (node (ref "Q3") (pin "3") (pinfunction "S_3") (pintype "unspecified"))
      (node (ref "Q4") (pin "5") (pinfunction "D_5") (pintype "unspecified"))
      (node (ref "Q4") (pin "6") (pinfunction "D_6") (pintype "unspecified"))
      (node (ref "Q4") (pin "7") (pinfunction "D_7") (pintype "unspecified"))
      (node (ref "Q4") (pin "8") (pinfunction "D_8") (pintype "unspecified"))
      (node (ref "Q4") (pin "9") (pinfunction "D_9") (pintype "unspecified"))
      (node (ref "R4") (pin "2") (pinfunction "2_2") (pintype "input"))
      (node (ref "U17") (pin "15") (pinfunction "VS2_15") (pintype "unspecified"))
    )
    (net (code "81") (name "VSB2") (class "Default")
      (node (ref "C35") (pin "2") (pinfunction "2_2") (pintype "input"))
      (node (ref "Q10") (pin "5") (pinfunction "D_5") (pintype "unspecified"))
      (node (ref "Q10") (pin "6") (pinfunction "D_6") (pintype "unspecified"))
      (node (ref "Q10") (pin "7") (pinfunction "D_7") (pintype "unspecified"))
      (node (ref "Q10") (pin "8") (pinfunction "D_8") (pintype "unspecified"))
      (node (ref "Q10") (pin "9") (pinfunction "D_9") (pintype "unspecified"))
      (node (ref "Q9") (pin "1") (pinfunction "S_1") (pintype "unspecified"))
      (node (ref "Q9") (pin "2") (pinfunction "S_2") (pintype "unspecified"))
      (node (ref "Q9") (pin "3") (pinfunction "S_3") (pintype "unspecified"))
      (node (ref "R24") (pin "2") (pinfunction "2_2") (pintype "input"))
      (node (ref "U28") (pin "15") (pinfunction "VS2_15") (pintype "unspecified"))
    )
    (net (code "82") (name "VSC1") (class "Default")
      (node (ref "C18") (pin "2") (pinfunction "2_2") (pintype "input"))
      (node (ref "Q5") (pin "1") (pinfunction "S_1") (pintype "unspecified"))
      (node (ref "Q5") (pin "2") (pinfunction "S_2") (pintype "unspecified"))
      (node (ref "Q5") (pin "3") (pinfunction "S_3") (pintype "unspecified"))
      (node (ref "Q6") (pin "5") (pinfunction "D_5") (pintype "unspecified"))
      (node (ref "Q6") (pin "6") (pinfunction "D_6") (pintype "unspecified"))
      (node (ref "Q6") (pin "7") (pinfunction "D_7") (pintype "unspecified"))
      (node (ref "Q6") (pin "8") (pinfunction "D_8") (pintype "unspecified"))
      (node (ref "Q6") (pin "9") (pinfunction "D_9") (pintype "unspecified"))
      (node (ref "R6") (pin "2") (pinfunction "2_2") (pintype "input"))
      (node (ref "U17") (pin "12") (pinfunction "VS3_12") (pintype "unspecified"))
    )
    (net (code "83") (name "VSC2") (class "Default")
      (node (ref "C36") (pin "2") (pinfunction "2_2") (pintype "input"))
      (node (ref "Q11") (pin "1") (pinfunction "S_1") (pintype "unspecified"))
      (node (ref "Q11") (pin "2") (pinfunction "S_2") (pintype "unspecified"))
      (node (ref "Q11") (pin "3") (pinfunction "S_3") (pintype "unspecified"))
      (node (ref "Q12") (pin "5") (pinfunction "D_5") (pintype "unspecified"))
      (node (ref "Q12") (pin "6") (pinfunction "D_6") (pintype "unspecified"))
      (node (ref "Q12") (pin "7") (pinfunction "D_7") (pintype "unspecified"))
      (node (ref "Q12") (pin "8") (pinfunction "D_8") (pintype "unspecified"))
      (node (ref "Q12") (pin "9") (pinfunction "D_9") (pintype "unspecified"))
      (node (ref "R26") (pin "2") (pinfunction "2_2") (pintype "input"))
      (node (ref "U28") (pin "12") (pinfunction "VS3_12") (pintype "unspecified"))
    )
    (net (code "84") (name "unconnected-(U15-CAN_RX_3{slash}CAN2_RX_3{slash}RXD2_2{slash}P4.6-Pad42)") (class "Default")
      (node (ref "U15") (pin "42") (pinfunction "CAN_RX_3/CAN2_RX_3/RXD2_2/P4.6_42") (pintype "unspecified"))
    )
    (net (code "85") (name "unconnected-(U15-CAN_RX_3{slash}WR{slash}P4.2-Pad30)") (class "Default")
      (node (ref "U15") (pin "30") (pinfunction "CAN_RX_3/WR/P4.2_30") (pintype "unspecified"))
    )
    (net (code "86") (name "unconnected-(U15-CAN_TX_3{slash}ALE{slash}P4.5-Pad41)") (class "Default")
      (node (ref "U15") (pin "41") (pinfunction "CAN_TX_3/ALE/P4.5_41") (pintype "unspecified"))
    )
    (net (code "87") (name "unconnected-(U15-CAN_TX{slash}PWM6_3{slash}TXD3{slash}ADC9{slash}AD1{slash}P0.1-Pad44)") (class "Default")
      (node (ref "U15") (pin "44") (pinfunction "CAN_TX/PWM6_3/TXD3/ADC9/AD1/P0.1_44") (pintype "unspecified"))
    )
    (net (code "88") (name "unconnected-(U15-LIN_RX_2{slash}CAN2_RX_2{slash}RXD4_2{slash}P5.2-Pad48)") (class "Default")
      (node (ref "U15") (pin "48") (pinfunction "LIN_RX_2/CAN2_RX_2/RXD4_2/P5.2_48") (pintype "unspecified"))
    )
    (net (code "89") (name "unconnected-(U15-LIN_RX{slash}CAN2_RX{slash}PWM7_3{slash}RXD4{slash}ADC10{slash}AD2{slash}P0.2-Pad45)") (class "Default")
      (node (ref "U15") (pin "45") (pinfunction "LIN_RX/CAN2_RX/PWM7_3/RXD4/ADC10/AD2/P0.2_45") (pintype "unspecified"))
    )
    (net (code "90") (name "unconnected-(U15-P0.5{slash}AD5{slash}ADC13{slash}T3CLKO-Pad2)") (class "Default")
      (node (ref "U15") (pin "2") (pinfunction "P0.5/AD5/ADC13/T3CLKO_2") (pintype "unspecified"))
    )
    (net (code "91") (name "unconnected-(U15-P0.6{slash}AD6{slash}ADC14{slash}T4{slash}PWMFLT2_2-Pad3)") (class "Default")
      (node (ref "U15") (pin "3") (pinfunction "P0.6/AD6/ADC14/T4/PWMFLT2_2_3") (pintype "unspecified"))
    )
    (net (code "92") (name "unconnected-(U15-P0.7{slash}AD7{slash}T4CLKO-Pad4)") (class "Default")
      (node (ref "U15") (pin "4") (pinfunction "P0.7/AD7/T4CLKO_4") (pintype "unspecified"))
    )
    (net (code "93") (name "unconnected-(U15-P1.0{slash}ADC0{slash}PWM1P{slash}RXD2-Pad5)") (class "Default")
      (node (ref "U15") (pin "5") (pinfunction "P1.0/ADC0/PWM1P/RXD2_5") (pintype "unspecified"))
    )
    (net (code "94") (name "unconnected-(U15-P1.1{slash}ADC1{slash}PWM1N{slash}TXD2-Pad6)") (class "Default")
      (node (ref "U15") (pin "6") (pinfunction "P1.1/ADC1/PWM1N/TXD2_6") (pintype "unspecified"))
    )
    (net (code "95") (name "unconnected-(U15-P1.3{slash}ADC3{slash}MOSI{slash}S2MOSI{slash}S1MOSI{slash}PWM2N{slash}T2CLKO-Pad12)") (class "Default")
      (node (ref "U15") (pin "12") (pinfunction "P1.3/ADC3/MOSI/S2MOSI/S1MOSI/PWM2N/T2CLKO_12") (pintype "unspecified"))
    )
    (net (code "96") (name "unconnected-(U15-P1.4{slash}ADC4{slash}PWM3P{slash}MISO{slash}S1MISO{slash}S2MISO{slash}SDA-Pad8)") (class "Default")
      (node (ref "U15") (pin "8") (pinfunction "P1.4/ADC4/PWM3P/MISO/S1MISO/S2MISO/SDA_8") (pintype "unspecified"))
    )
    (net (code "97") (name "unconnected-(U15-P1.5{slash}ADC5{slash}PWM3N{slash}SCLK{slash}S1CLK{slash}S2CLK{slash}SCL-Pad9)") (class "Default")
      (node (ref "U15") (pin "9") (pinfunction "P1.5/ADC5/PWM3N/SCLK/S1CLK/S2CLK/SCL_9") (pintype "unspecified"))
    )
    (net (code "98") (name "unconnected-(U15-P1.6{slash}ADC6{slash}RXD_3{slash}PWM4P{slash}MCLKO_2{slash}XTALO-Pad10)") (class "Default")
      (node (ref "U15") (pin "10") (pinfunction "P1.6/ADC6/RXD_3/PWM4P/MCLKO_2/XTALO_10") (pintype "unspecified"))
    )
    (net (code "99") (name "unconnected-(U15-P1.7{slash}ADC7{slash}TXD_3{slash}PWM4N{slash}PWM5_2{slash}XTALI-Pad11)") (class "Default")
      (node (ref "U15") (pin "11") (pinfunction "P1.7/ADC7/TXD_3/PWM4N/PWM5_2/XTALI_11") (pintype "unspecified"))
    )
    (net (code "100") (name "unconnected-(U15-P3.2{slash}INT0{slash}SCLK_4{slash}SCL_4{slash}PWMETI{slash}PWMETI2-Pad21)") (class "Default")
      (node (ref "U15") (pin "21") (pinfunction "P3.2/INT0/SCLK_4/SCL_4/PWMETI/PWMETI2_21") (pintype "unspecified"))
    )
    (net (code "101") (name "unconnected-(U15-P3.3{slash}INT1{slash}MISO_4{slash}SDA_4{slash}PWM4N_4{slash}PWM7_2-Pad22)") (class "Default")
      (node (ref "U15") (pin "22") (pinfunction "P3.3/INT1/MISO_4/SDA_4/PWM4N_4/PWM7_2_22") (pintype "unspecified"))
    )
    (net (code "102") (name "unconnected-(U15-P3.4{slash}T0{slash}T1CLKO{slash}MOSI_4{slash}PWM4P_4{slash}PWM8_2{slash}CMPO-Pad23)") (class "Default")
      (node (ref "U15") (pin "23") (pinfunction "P3.4/T0/T1CLKO/MOSI_4/PWM4P_4/PWM8_2/CMPO_23") (pintype "unspecified"))
    )
    (net (code "103") (name "unconnected-(U15-P4.0{slash}MOSI_3{slash}S1MOSI_3{slash}S2MOSI_3-Pad18)") (class "Default")
      (node (ref "U15") (pin "18") (pinfunction "P4.0/MOSI_3/S1MOSI_3/S2MOSI_3_18") (pintype "unspecified"))
    )
    (net (code "104") (name "unconnected-(U15-P4.7{slash}TXD2_2{slash}CAN2_TX_3{slash}LIN_TX_3-Pad7)") (class "Default")
      (node (ref "U15") (pin "7") (pinfunction "P4.7/TXD2_2/CAN2_TX_3/LIN_TX_3_7") (pintype "unspecified"))
    )
    (net (code "105") (name "unconnected-(U15-P5.3{slash}TXD4_2{slash}CAN2_TX_2{slash}LIN_TX_2-Pad1)") (class "Default")
      (node (ref "U15") (pin "1") (pinfunction "P5.3/TXD4_2/CAN2_TX_2/LIN_TX_2_1") (pintype "unspecified"))
    )
    (net (code "106") (name "unconnected-(U15-P5.4{slash}ADC2{slash}PWM2P{slash}PWM6_2{slash}RST{slash}MCLKO{slash}SS_3{slash}S1SS_3{slash}S2SS_3{slash}T2-Pad14)") (class "Default")
      (node (ref "U15") (pin "14") (pinfunction "P5.4/ADC2/PWM2P/PWM6_2/RST/MCLKO/SS_3/S1SS_3/S2SS_3/T2_14") (pintype "unspecified"))
    )
    (net (code "107") (name "unconnected-(U15-PWM4N_2{slash}A15{slash}P2.7-Pad40)") (class "Default")
      (node (ref "U15") (pin "40") (pinfunction "PWM4N_2/A15/P2.7_40") (pintype "unspecified"))
    )
    (net (code "108") (name "unconnected-(U15-PWM4P_2{slash}A14{slash}P2.6-Pad39)") (class "Default")
      (node (ref "U15") (pin "39") (pinfunction "PWM4P_2/A14/P2.6_39") (pintype "unspecified"))
    )
    (net (code "109") (name "unconnected-(U15-PWMETI_3{slash}CMPO_2{slash}S2MISO_3{slash}S1MISO_3{slash}MISO_3{slash}P4.1-Pad29)") (class "Default")
      (node (ref "U15") (pin "29") (pinfunction "PWMETI_3/CMPO_2/S2MISO_3/S1MISO_3/MISO_3/P4.1_29") (pintype "unspecified"))
    )
    (net (code "110") (name "unconnected-(U15-PWMFLT{slash}SS_4{slash}T0CLKO{slash}T1{slash}P3.5-Pad26)") (class "Default")
      (node (ref "U15") (pin "26") (pinfunction "PWMFLT/SS_4/T0CLKO/T1/P3.5_26") (pintype "unspecified"))
    )
    (net (code "111") (name "unconnected-(U15-S2SCLK_3{slash}S1SCLK_3{slash}SCLK{slash}RXD_4{slash}P4.3-Pad31)") (class "Default")
      (node (ref "U15") (pin "31") (pinfunction "S2SCLK_3/S1SCLK_3/SCLK/RXD_4/P4.3_31") (pintype "unspecified"))
    )
    (net (code "112") (name "unconnected-(U15-T3{slash}ADC12{slash}AD4{slash}P0.4-Pad47)") (class "Default")
      (node (ref "U15") (pin "47") (pinfunction "T3/ADC12/AD4/P0.4_47") (pintype "unspecified"))
    )
    (net (code "113") (name "unconnected-(U17-NC-Pad5)") (class "Default")
      (node (ref "U17") (pin "5") (pinfunction "NC_5") (pintype "unspecified+no_connect"))
    )
    (net (code "114") (name "unconnected-(U17-NC-Pad7)") (class "Default")
      (node (ref "U17") (pin "7") (pinfunction "NC_7") (pintype "unspecified+no_connect"))
    )
    (net (code "115") (name "unconnected-(U17-NC-Pad8)") (class "Default")
      (node (ref "U17") (pin "8") (pinfunction "NC_8") (pintype "unspecified+no_connect"))
    )
    (net (code "116") (name "unconnected-(U17-NC-Pad21)") (class "Default")
      (node (ref "U17") (pin "21") (pinfunction "NC_21") (pintype "unspecified+no_connect"))
    )
    (net (code "117") (name "unconnected-(U20-Pad1)") (class "Default")
      (node (ref "U20") (pin "1") (pinfunction "1_1") (pintype "input"))
    )
    (net (code "118") (name "unconnected-(U21-Pad1)") (class "Default")
      (node (ref "U21") (pin "1") (pinfunction "1_1") (pintype "input"))
    )
    (net (code "119") (name "unconnected-(U22-CAN_RX_3{slash}CAN2_RX_3{slash}RXD2_2{slash}P4.6-Pad42)") (class "Default")
      (node (ref "U22") (pin "42") (pinfunction "CAN_RX_3/CAN2_RX_3/RXD2_2/P4.6_42") (pintype "unspecified"))
    )
    (net (code "120") (name "unconnected-(U22-CAN_RX_3{slash}WR{slash}P4.2-Pad30)") (class "Default")
      (node (ref "U22") (pin "30") (pinfunction "CAN_RX_3/WR/P4.2_30") (pintype "unspecified"))
    )
    (net (code "121") (name "unconnected-(U22-CAN_TX_3{slash}ALE{slash}P4.5-Pad41)") (class "Default")
      (node (ref "U22") (pin "41") (pinfunction "CAN_TX_3/ALE/P4.5_41") (pintype "unspecified"))
    )
    (net (code "122") (name "unconnected-(U22-CAN_TX{slash}PWM6_3{slash}TXD3{slash}ADC9{slash}AD1{slash}P0.1-Pad44)") (class "Default")
      (node (ref "U22") (pin "44") (pinfunction "CAN_TX/PWM6_3/TXD3/ADC9/AD1/P0.1_44") (pintype "unspecified"))
    )
    (net (code "123") (name "unconnected-(U22-LIN_RX_2{slash}CAN2_RX_2{slash}RXD4_2{slash}P5.2-Pad48)") (class "Default")
      (node (ref "U22") (pin "48") (pinfunction "LIN_RX_2/CAN2_RX_2/RXD4_2/P5.2_48") (pintype "unspecified"))
    )
    (net (code "124") (name "unconnected-(U22-LIN_RX{slash}CAN2_RX{slash}PWM7_3{slash}RXD4{slash}ADC10{slash}AD2{slash}P0.2-Pad45)") (class "Default")
      (node (ref "U22") (pin "45") (pinfunction "LIN_RX/CAN2_RX/PWM7_3/RXD4/ADC10/AD2/P0.2_45") (pintype "unspecified"))
    )
    (net (code "125") (name "unconnected-(U22-P0.5{slash}AD5{slash}ADC13{slash}T3CLKO-Pad2)") (class "Default")
      (node (ref "U22") (pin "2") (pinfunction "P0.5/AD5/ADC13/T3CLKO_2") (pintype "unspecified"))
    )
    (net (code "126") (name "unconnected-(U22-P0.6{slash}AD6{slash}ADC14{slash}T4{slash}PWMFLT2_2-Pad3)") (class "Default")
      (node (ref "U22") (pin "3") (pinfunction "P0.6/AD6/ADC14/T4/PWMFLT2_2_3") (pintype "unspecified"))
    )
    (net (code "127") (name "unconnected-(U22-P0.7{slash}AD7{slash}T4CLKO-Pad4)") (class "Default")
      (node (ref "U22") (pin "4") (pinfunction "P0.7/AD7/T4CLKO_4") (pintype "unspecified"))
    )
    (net (code "128") (name "unconnected-(U22-P1.0{slash}ADC0{slash}PWM1P{slash}RXD2-Pad5)") (class "Default")
      (node (ref "U22") (pin "5") (pinfunction "P1.0/ADC0/PWM1P/RXD2_5") (pintype "unspecified"))
    )
    (net (code "129") (name "unconnected-(U22-P1.1{slash}ADC1{slash}PWM1N{slash}TXD2-Pad6)") (class "Default")
      (node (ref "U22") (pin "6") (pinfunction "P1.1/ADC1/PWM1N/TXD2_6") (pintype "unspecified"))
    )
    (net (code "130") (name "unconnected-(U22-P1.3{slash}ADC3{slash}MOSI{slash}S2MOSI{slash}S1MOSI{slash}PWM2N{slash}T2CLKO-Pad12)") (class "Default")
      (node (ref "U22") (pin "12") (pinfunction "P1.3/ADC3/MOSI/S2MOSI/S1MOSI/PWM2N/T2CLKO_12") (pintype "unspecified"))
    )
    (net (code "131") (name "unconnected-(U22-P1.4{slash}ADC4{slash}PWM3P{slash}MISO{slash}S1MISO{slash}S2MISO{slash}SDA-Pad8)") (class "Default")
      (node (ref "U22") (pin "8") (pinfunction "P1.4/ADC4/PWM3P/MISO/S1MISO/S2MISO/SDA_8") (pintype "unspecified"))
    )
    (net (code "132") (name "unconnected-(U22-P1.5{slash}ADC5{slash}PWM3N{slash}SCLK{slash}S1CLK{slash}S2CLK{slash}SCL-Pad9)") (class "Default")
      (node (ref "U22") (pin "9") (pinfunction "P1.5/ADC5/PWM3N/SCLK/S1CLK/S2CLK/SCL_9") (pintype "unspecified"))
    )
    (net (code "133") (name "unconnected-(U22-P1.6{slash}ADC6{slash}RXD_3{slash}PWM4P{slash}MCLKO_2{slash}XTALO-Pad10)") (class "Default")
      (node (ref "U22") (pin "10") (pinfunction "P1.6/ADC6/RXD_3/PWM4P/MCLKO_2/XTALO_10") (pintype "unspecified"))
    )
    (net (code "134") (name "unconnected-(U22-P1.7{slash}ADC7{slash}TXD_3{slash}PWM4N{slash}PWM5_2{slash}XTALI-Pad11)") (class "Default")
      (node (ref "U22") (pin "11") (pinfunction "P1.7/ADC7/TXD_3/PWM4N/PWM5_2/XTALI_11") (pintype "unspecified"))
    )
    (net (code "135") (name "unconnected-(U22-P3.2{slash}INT0{slash}SCLK_4{slash}SCL_4{slash}PWMETI{slash}PWMETI2-Pad21)") (class "Default")
      (node (ref "U22") (pin "21") (pinfunction "P3.2/INT0/SCLK_4/SCL_4/PWMETI/PWMETI2_21") (pintype "unspecified"))
    )
    (net (code "136") (name "unconnected-(U22-P3.3{slash}INT1{slash}MISO_4{slash}SDA_4{slash}PWM4N_4{slash}PWM7_2-Pad22)") (class "Default")
      (node (ref "U22") (pin "22") (pinfunction "P3.3/INT1/MISO_4/SDA_4/PWM4N_4/PWM7_2_22") (pintype "unspecified"))
    )
    (net (code "137") (name "unconnected-(U22-P3.4{slash}T0{slash}T1CLKO{slash}MOSI_4{slash}PWM4P_4{slash}PWM8_2{slash}CMPO-Pad23)") (class "Default")
      (node (ref "U22") (pin "23") (pinfunction "P3.4/T0/T1CLKO/MOSI_4/PWM4P_4/PWM8_2/CMPO_23") (pintype "unspecified"))
    )
    (net (code "138") (name "unconnected-(U22-P4.0{slash}MOSI_3{slash}S1MOSI_3{slash}S2MOSI_3-Pad18)") (class "Default")
      (node (ref "U22") (pin "18") (pinfunction "P4.0/MOSI_3/S1MOSI_3/S2MOSI_3_18") (pintype "unspecified"))
    )
    (net (code "139") (name "unconnected-(U22-P4.7{slash}TXD2_2{slash}CAN2_TX_3{slash}LIN_TX_3-Pad7)") (class "Default")
      (node (ref "U22") (pin "7") (pinfunction "P4.7/TXD2_2/CAN2_TX_3/LIN_TX_3_7") (pintype "unspecified"))
    )
    (net (code "140") (name "unconnected-(U22-P5.3{slash}TXD4_2{slash}CAN2_TX_2{slash}LIN_TX_2-Pad1)") (class "Default")
      (node (ref "U22") (pin "1") (pinfunction "P5.3/TXD4_2/CAN2_TX_2/LIN_TX_2_1") (pintype "unspecified"))
    )
    (net (code "141") (name "unconnected-(U22-P5.4{slash}ADC2{slash}PWM2P{slash}PWM6_2{slash}RST{slash}MCLKO{slash}SS_3{slash}S1SS_3{slash}S2SS_3{slash}T2-Pad14)") (class "Default")
      (node (ref "U22") (pin "14") (pinfunction "P5.4/ADC2/PWM2P/PWM6_2/RST/MCLKO/SS_3/S1SS_3/S2SS_3/T2_14") (pintype "unspecified"))
    )
    (net (code "142") (name "unconnected-(U22-PWM4N_2{slash}A15{slash}P2.7-Pad40)") (class "Default")
      (node (ref "U22") (pin "40") (pinfunction "PWM4N_2/A15/P2.7_40") (pintype "unspecified"))
    )
    (net (code "143") (name "unconnected-(U22-PWM4P_2{slash}A14{slash}P2.6-Pad39)") (class "Default")
      (node (ref "U22") (pin "39") (pinfunction "PWM4P_2/A14/P2.6_39") (pintype "unspecified"))
    )
    (net (code "144") (name "unconnected-(U22-PWMETI_3{slash}CMPO_2{slash}S2MISO_3{slash}S1MISO_3{slash}MISO_3{slash}P4.1-Pad29)") (class "Default")
      (node (ref "U22") (pin "29") (pinfunction "PWMETI_3/CMPO_2/S2MISO_3/S1MISO_3/MISO_3/P4.1_29") (pintype "unspecified"))
    )
    (net (code "145") (name "unconnected-(U22-PWMFLT{slash}SS_4{slash}T0CLKO{slash}T1{slash}P3.5-Pad26)") (class "Default")
      (node (ref "U22") (pin "26") (pinfunction "PWMFLT/SS_4/T0CLKO/T1/P3.5_26") (pintype "unspecified"))
    )
    (net (code "146") (name "unconnected-(U22-S2SCLK_3{slash}S1SCLK_3{slash}SCLK{slash}RXD_4{slash}P4.3-Pad31)") (class "Default")
      (node (ref "U22") (pin "31") (pinfunction "S2SCLK_3/S1SCLK_3/SCLK/RXD_4/P4.3_31") (pintype "unspecified"))
    )
    (net (code "147") (name "unconnected-(U22-T3{slash}ADC12{slash}AD4{slash}P0.4-Pad47)") (class "Default")
      (node (ref "U22") (pin "47") (pinfunction "T3/ADC12/AD4/P0.4_47") (pintype "unspecified"))
    )
    (net (code "148") (name "unconnected-(U28-NC-Pad5)") (class "Default")
      (node (ref "U28") (pin "5") (pinfunction "NC_5") (pintype "unspecified+no_connect"))
    )
    (net (code "149") (name "unconnected-(U28-NC-Pad7)") (class "Default")
      (node (ref "U28") (pin "7") (pinfunction "NC_7") (pintype "unspecified+no_connect"))
    )
    (net (code "150") (name "unconnected-(U28-NC-Pad8)") (class "Default")
      (node (ref "U28") (pin "8") (pinfunction "NC_8") (pintype "unspecified+no_connect"))
    )
    (net (code "151") (name "unconnected-(U28-NC-Pad21)") (class "Default")
      (node (ref "U28") (pin "21") (pinfunction "NC_21") (pintype "unspecified+no_connect"))
    )
  )
)
